# MotorControlV4_5.net
KiCad netlist of a schematic drawn in Altium Designer
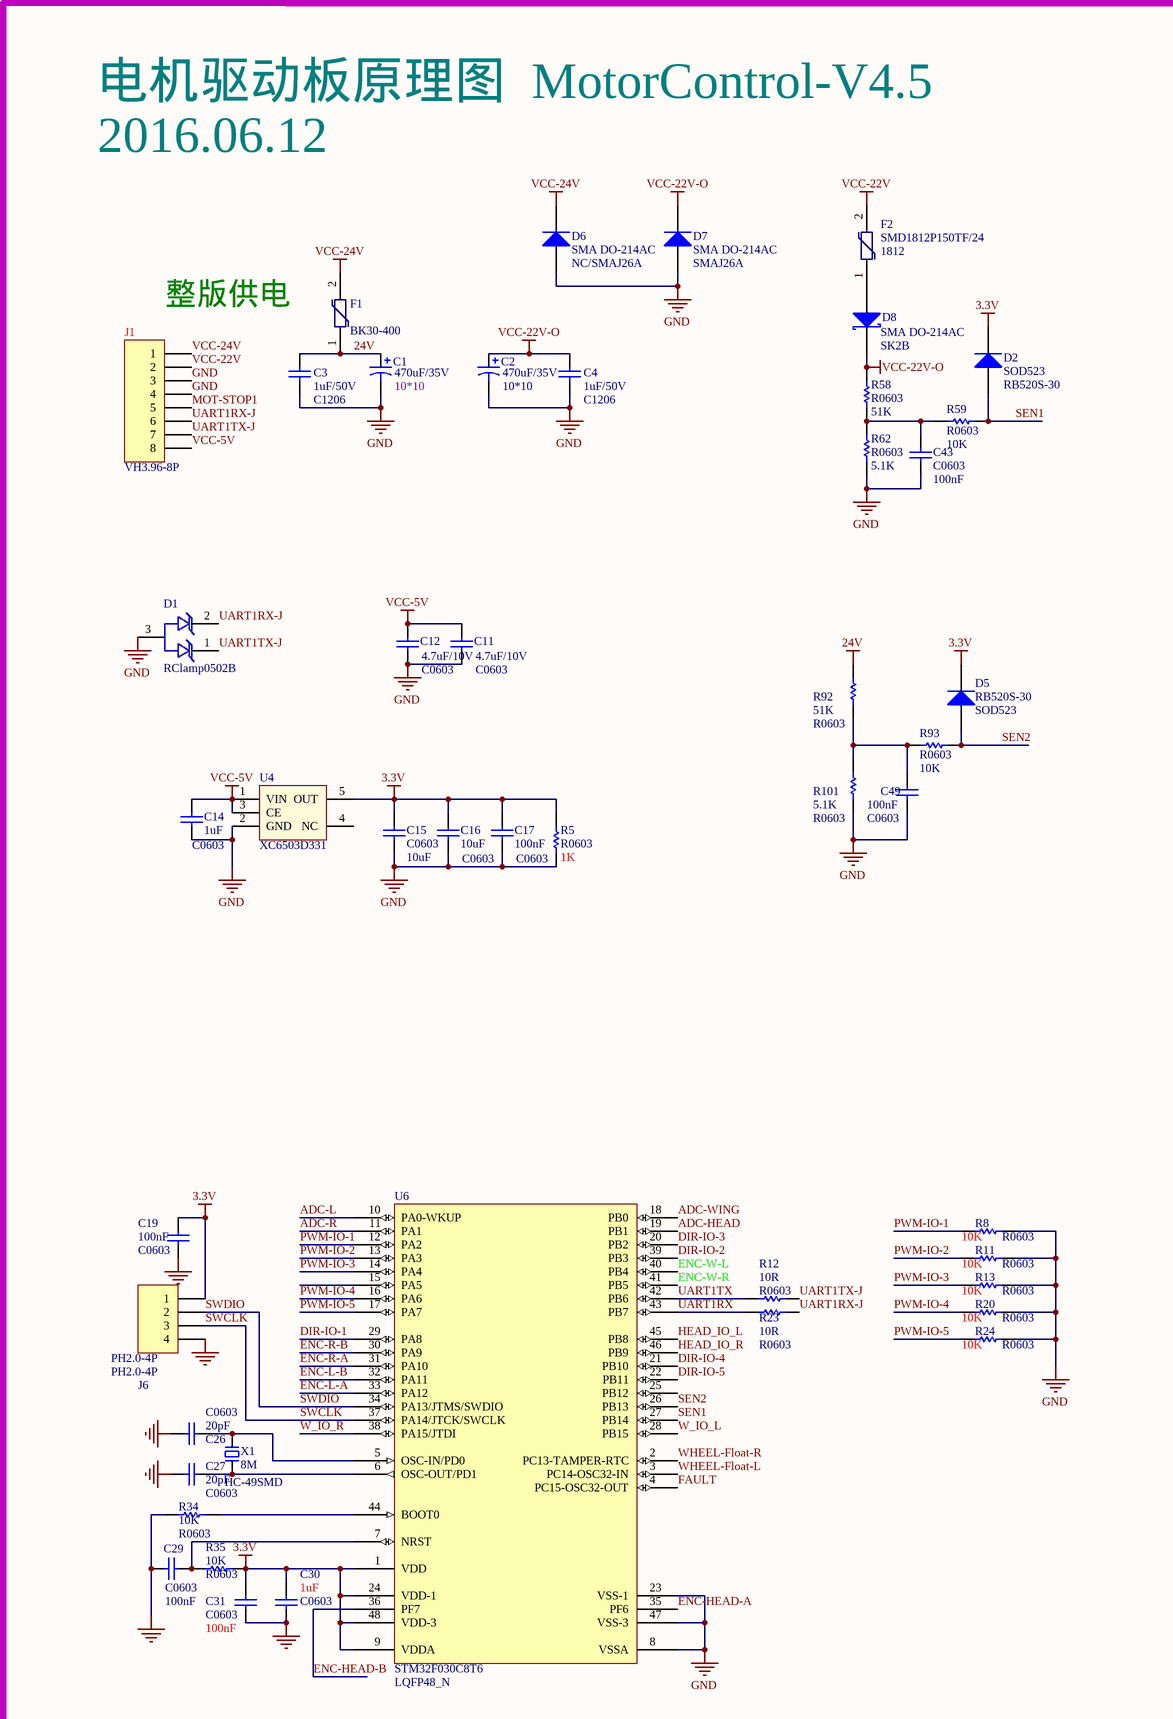
[diagram p0: MotorControlV4.5.SchDoc, top left]
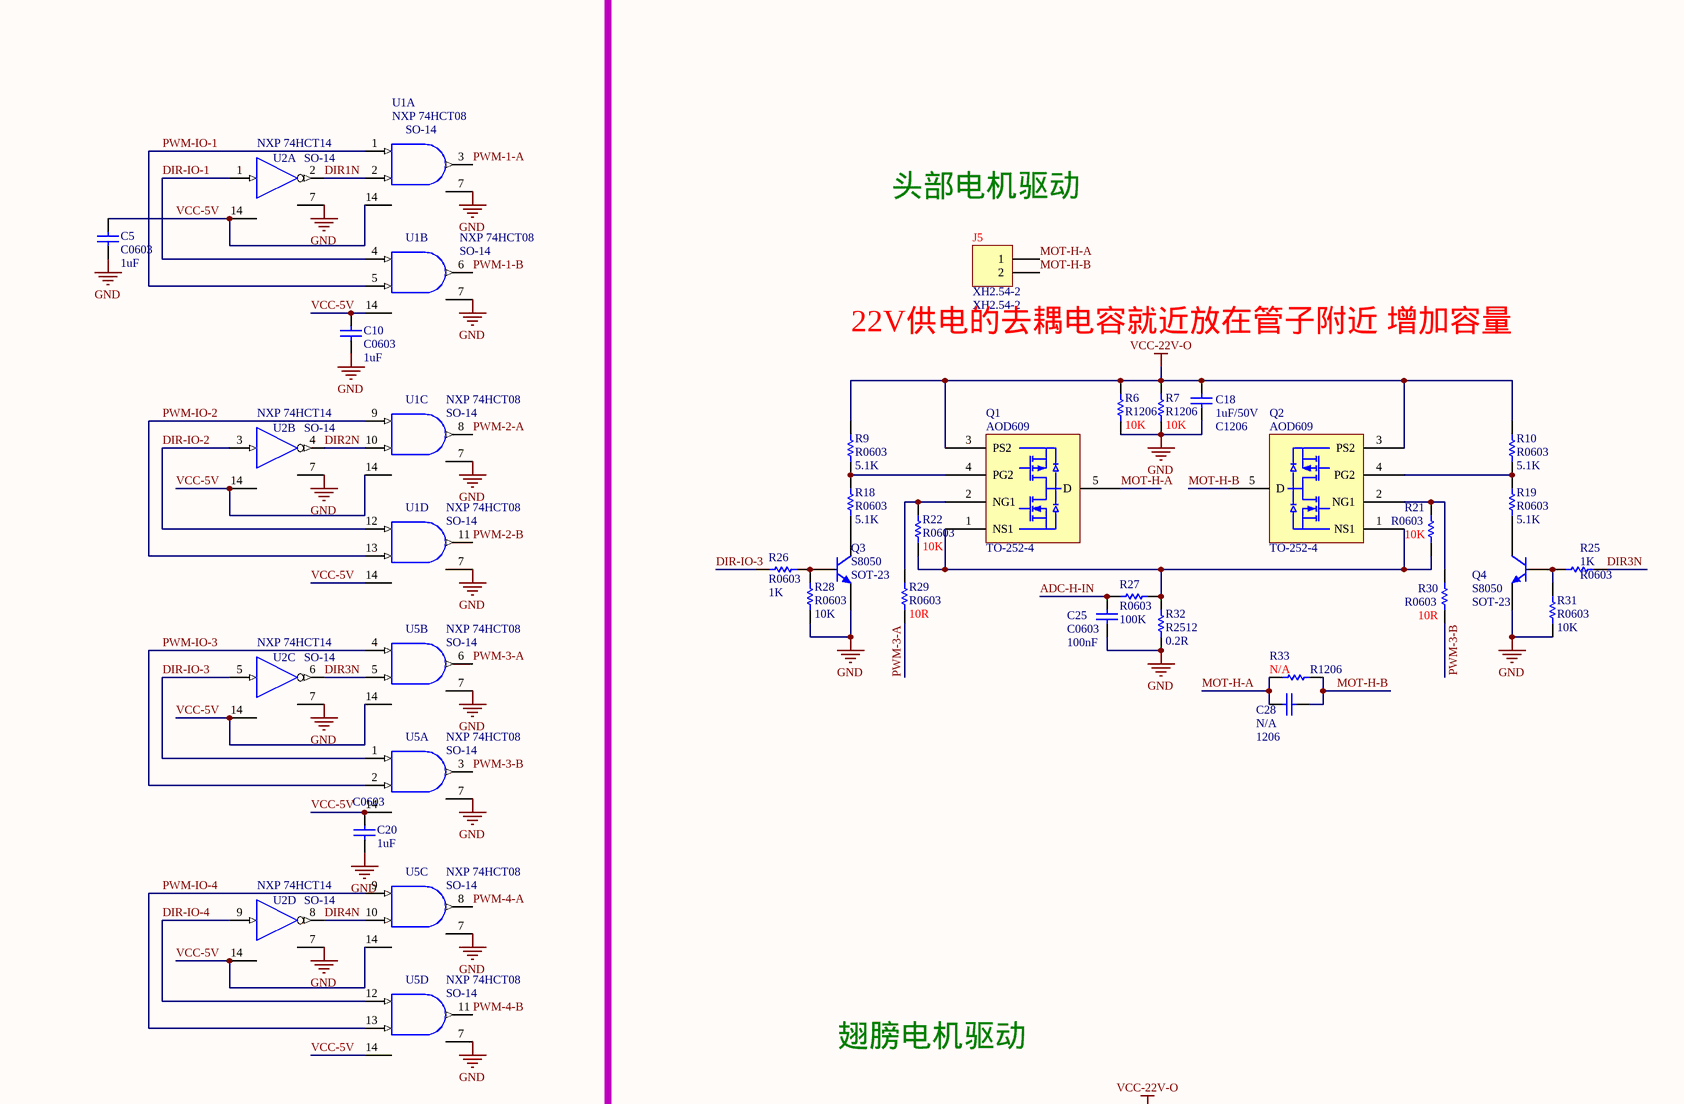
[diagram p1: MotorControlV4.5.SchDoc, top middle]
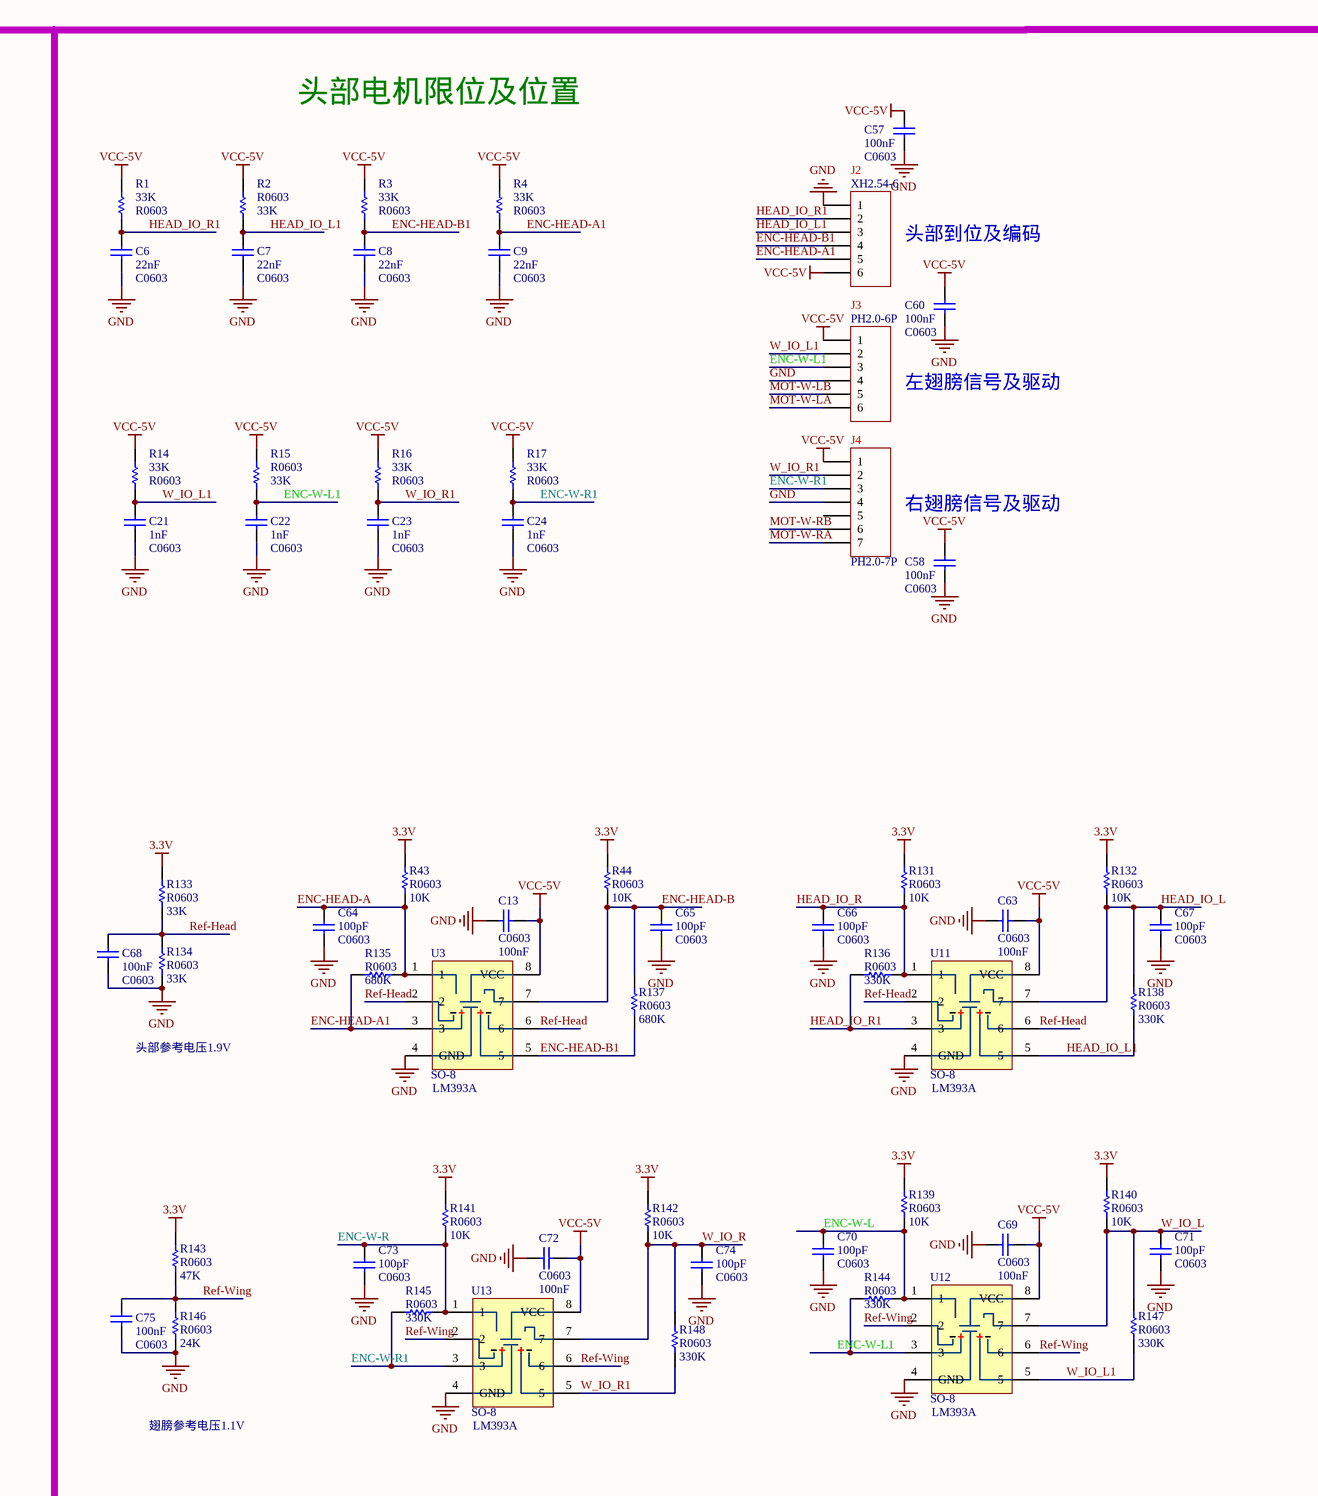
[diagram p2: MotorControlV4.5.SchDoc, top right]
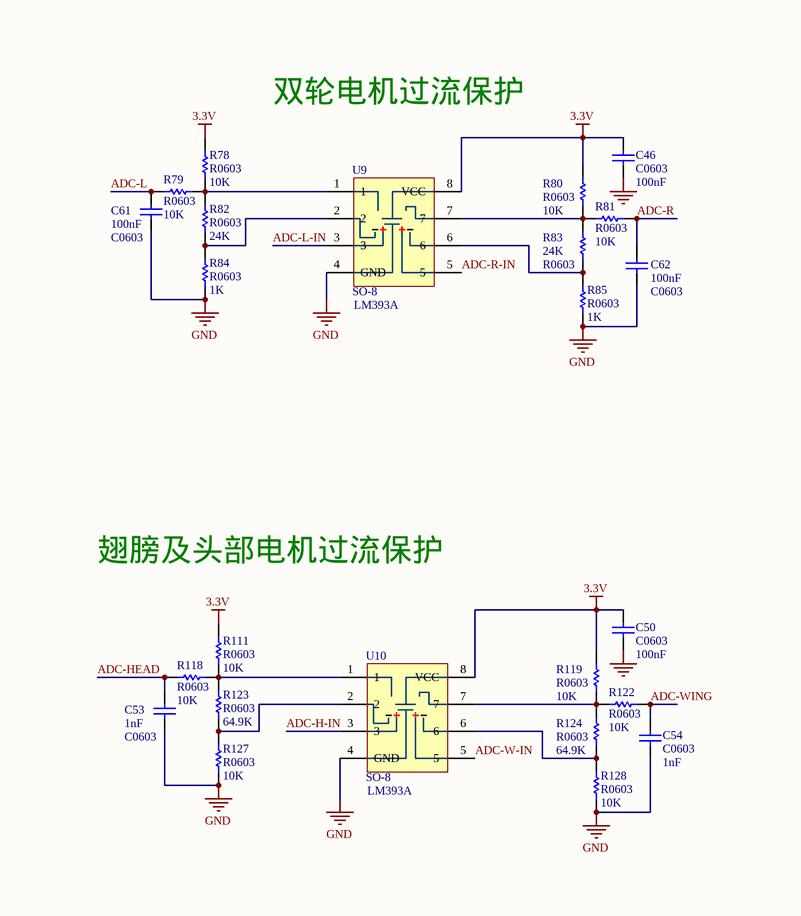
[diagram p3: MotorControlV4.5.SchDoc, bottom left]
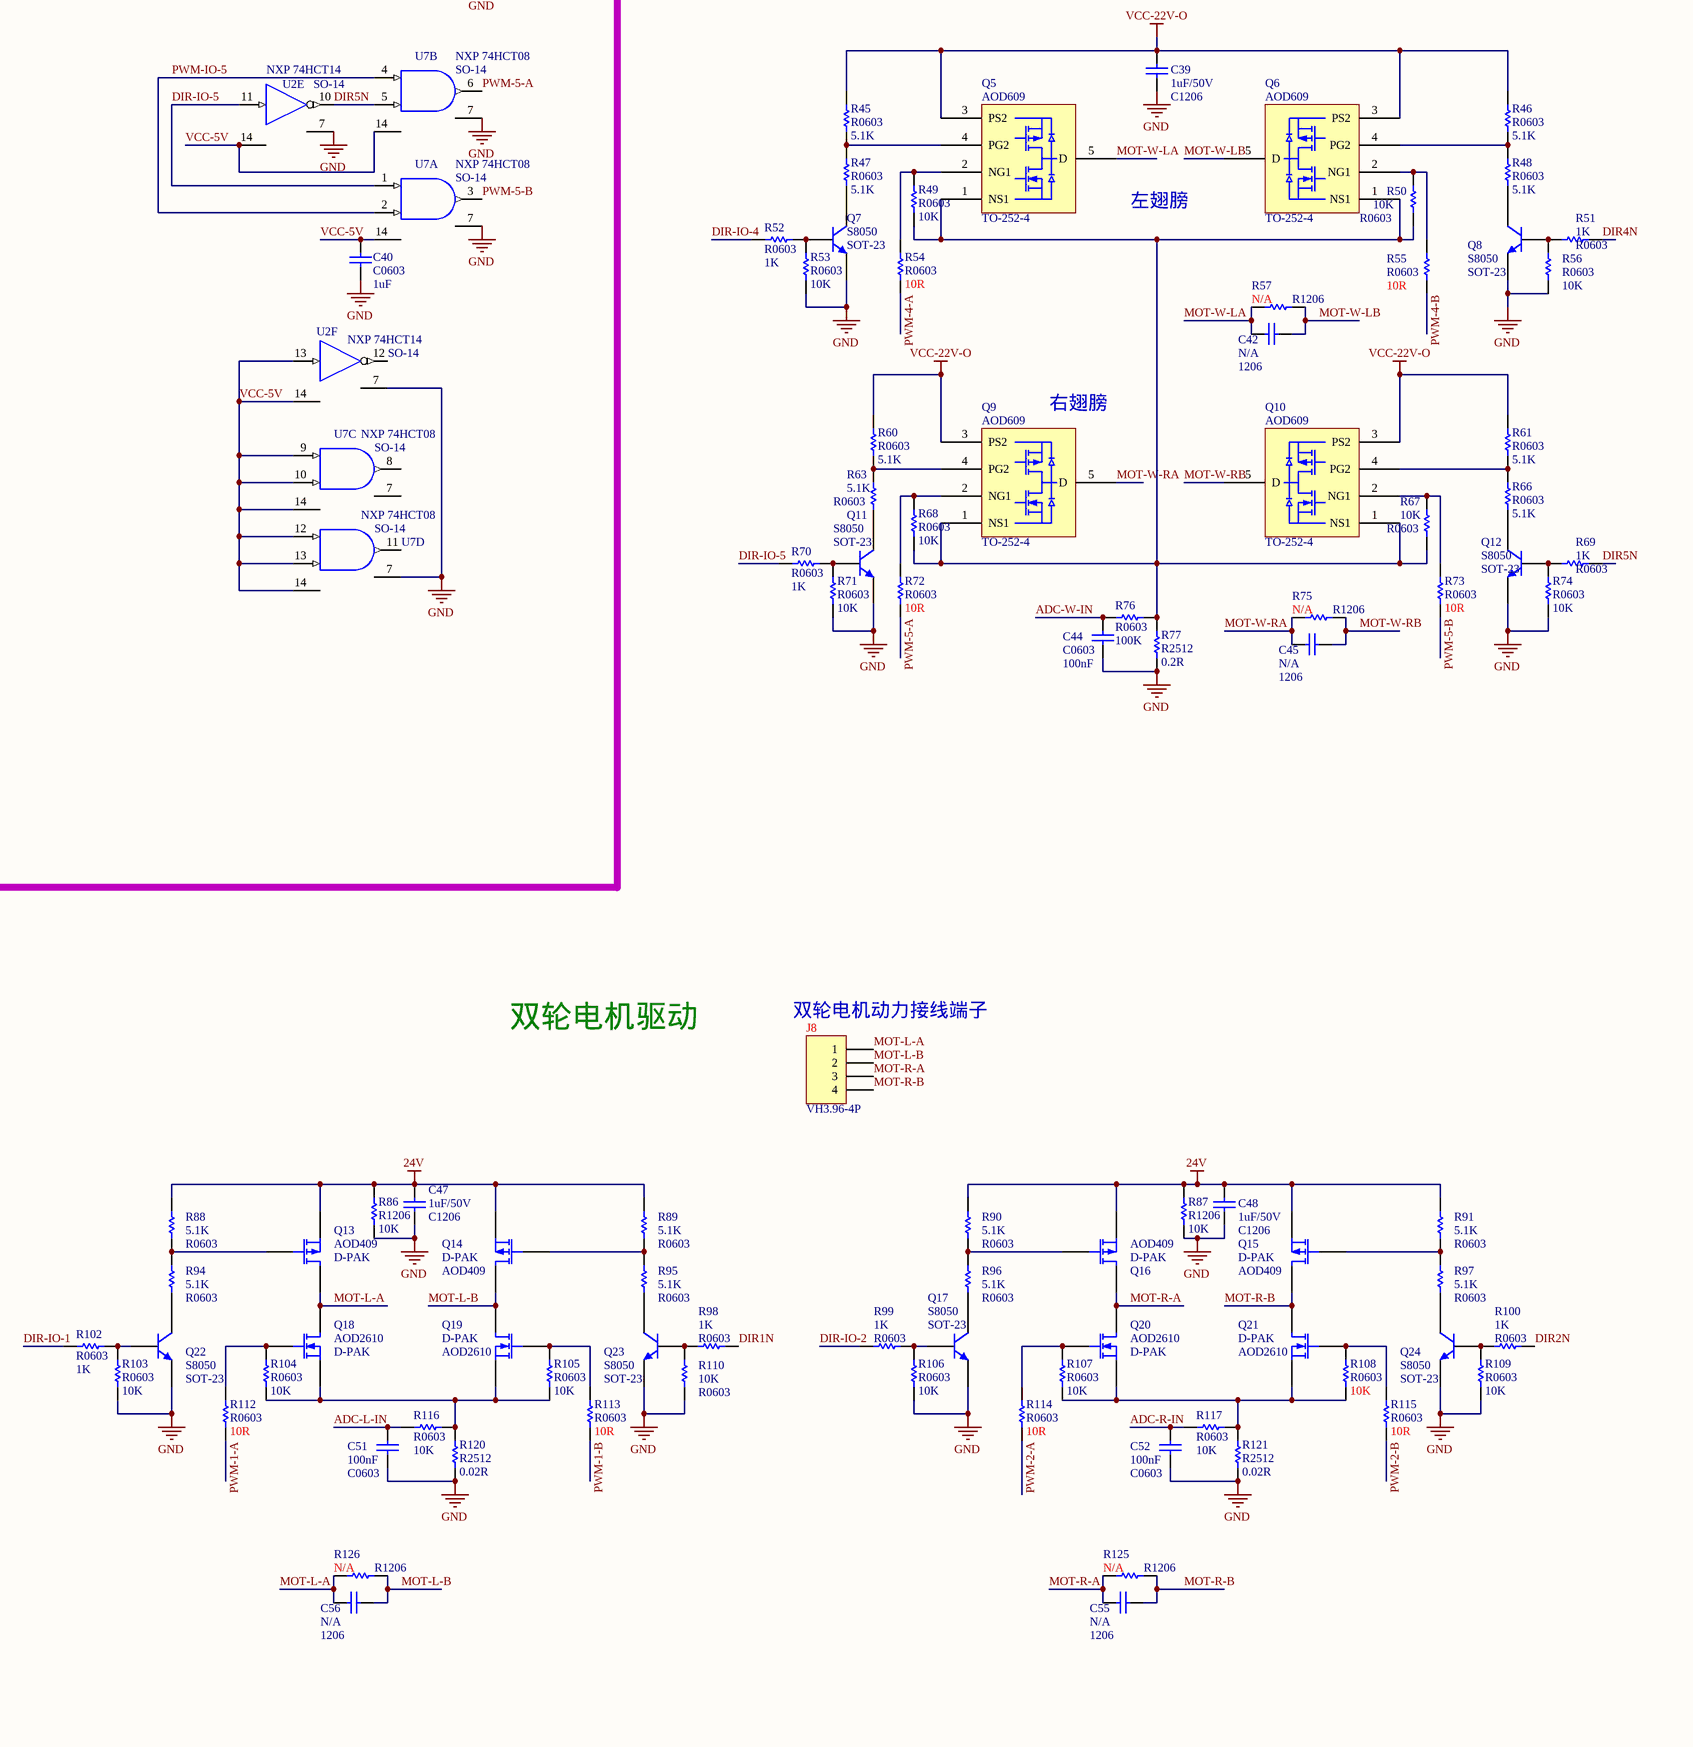
[diagram p4: MotorControlV4.5.SchDoc, bottom middle]
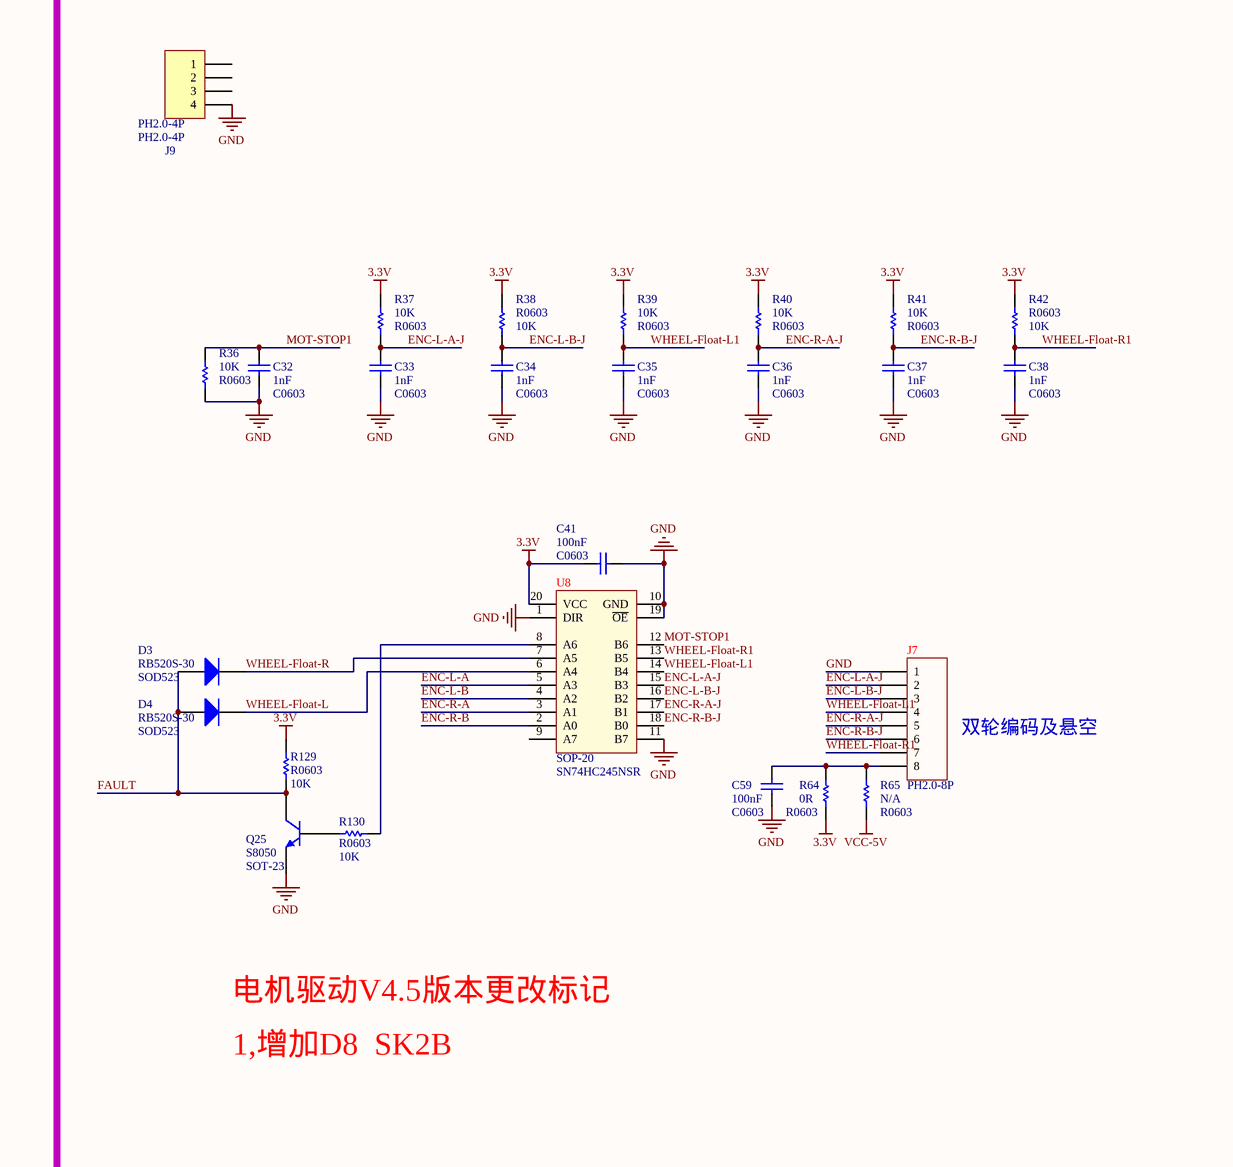
[diagram p5: MotorControlV4.5.SchDoc, bottom right]

(export (version "E")
  (design (tool "Eeschema 10.0.6"))
  (components
    (comp (ref "C1")
      (value "470uF/35V")
      (footprint "CAP_SO_10*10")
      (description "Polarized Capacitor (Surface Mount)")
      (fields (field (name "ALTIUM_VALUE") "10*10") (field (name "PUBLISHER") "Altium Limited"))
      (libsource (lib "Miscellaneous Devices") (part "Cap Pol3"))
    )
    (comp (ref "C2")
      (value "470uF/35V")
      (footprint "CAP_SO_10*10")
      (description "Polarized Capacitor (Surface Mount)")
      (fields (field (name "ALTIUM_VALUE") "10*10") (field (name "PUBLISHER") "Altium Limited"))
      (libsource (lib "Miscellaneous Devices") (part "Cap Pol3"))
    )
    (comp (ref "C3")
      (value "C1206")
      (footprint "1206")
      (description "Capacitor")
      (fields (field (name "ALTIUM_VALUE") "1uF/50V") (field (name "PUBLISHER") "Altium Limited"))
      (libsource (lib "Miscellaneous Devices") (part "Cap"))
    )
    (comp (ref "C4")
      (value "C1206")
      (footprint "1206")
      (description "Capacitor")
      (fields (field (name "ALTIUM_VALUE") "1uF/50V") (field (name "PUBLISHER") "Altium Limited"))
      (libsource (lib "Miscellaneous Devices") (part "Cap"))
    )
    (comp (ref "C5")
      (value "C0603")
      (footprint "C0603_M1608")
      (description "Capacitor")
      (fields (field (name "ALTIUM_VALUE") "1uF") (field (name "PUBLISHER") "Altium Limited"))
      (libsource (lib "Miscellaneous Devices") (part "Cap"))
    )
    (comp (ref "C6")
      (value "C0603")
      (footprint "C0603_M1608")
      (description "Capacitor")
      (fields (field (name "ALTIUM_VALUE") "22nF") (field (name "PUBLISHER") "Altium Limited"))
      (libsource (lib "Miscellaneous Devices") (part "Cap"))
    )
    (comp (ref "C7")
      (value "C0603")
      (footprint "C0603_M1608")
      (description "Capacitor")
      (fields (field (name "ALTIUM_VALUE") "22nF") (field (name "PUBLISHER") "Altium Limited"))
      (libsource (lib "Miscellaneous Devices") (part "Cap"))
    )
    (comp (ref "C8")
      (value "C0603")
      (footprint "C0603_M1608")
      (description "Capacitor")
      (fields (field (name "ALTIUM_VALUE") "22nF") (field (name "PUBLISHER") "Altium Limited"))
      (libsource (lib "Miscellaneous Devices") (part "Cap"))
    )
    (comp (ref "C9")
      (value "C0603")
      (footprint "C0603_M1608")
      (description "Capacitor")
      (fields (field (name "ALTIUM_VALUE") "22nF") (field (name "PUBLISHER") "Altium Limited"))
      (libsource (lib "Miscellaneous Devices") (part "Cap"))
    )
    (comp (ref "C10")
      (value "C0603")
      (footprint "C0603_M1608")
      (description "Capacitor")
      (fields (field (name "ALTIUM_VALUE") "1uF") (field (name "PUBLISHER") "Altium Limited"))
      (libsource (lib "Miscellaneous Devices") (part "Cap"))
    )
    (comp (ref "C11")
      (value "C0603")
      (footprint "C0603_M1608")
      (description "Capacitor")
      (fields (field (name "ALTIUM_VALUE") "4.7uF/10V") (field (name "PUBLISHER") "Altium Limited"))
      (libsource (lib "Miscellaneous Devices") (part "Cap"))
    )
    (comp (ref "C12")
      (value "C0603")
      (footprint "C0603_M1608")
      (description "Capacitor")
      (fields (field (name "ALTIUM_VALUE") "4.7uF/10V") (field (name "PUBLISHER") "Altium Limited"))
      (libsource (lib "Miscellaneous Devices") (part "Cap"))
    )
    (comp (ref "C13")
      (value "C0603")
      (footprint "C0603_M1608")
      (description "Capacitor")
      (fields (field (name "ALTIUM_VALUE") "100nF") (field (name "PUBLISHER") "Altium Limited"))
      (libsource (lib "Miscellaneous Devices") (part "Cap"))
    )
    (comp (ref "C14")
      (value "C0603")
      (footprint "C0603_M1608")
      (description "Capacitor")
      (fields (field (name "ALTIUM_VALUE") "1uF") (field (name "PUBLISHER") "Altium Limited"))
      (libsource (lib "Miscellaneous Devices") (part "Cap"))
    )
    (comp (ref "C15")
      (value "C0603")
      (footprint "C0603_M1608")
      (description "Capacitor")
      (fields (field (name "ALTIUM_VALUE") "10uF") (field (name "PUBLISHER") "Altium Limited"))
      (libsource (lib "Miscellaneous Devices") (part "Cap"))
    )
    (comp (ref "C16")
      (value "C0603")
      (footprint "C0603_M1608")
      (description "Capacitor")
      (fields (field (name "ALTIUM_VALUE") "10uF") (field (name "PUBLISHER") "Altium Limited"))
      (libsource (lib "Miscellaneous Devices") (part "Cap"))
    )
    (comp (ref "C17")
      (value "C0603")
      (footprint "C0603_M1608")
      (description "Capacitor")
      (fields (field (name "ALTIUM_VALUE") "100nF") (field (name "PUBLISHER") "Altium Limited"))
      (libsource (lib "Miscellaneous Devices") (part "Cap"))
    )
    (comp (ref "C18")
      (value "C1206")
      (footprint "1206")
      (description "Capacitor")
      (fields (field (name "ALTIUM_VALUE") "1uF/50V") (field (name "PUBLISHER") "Altium Limited"))
      (libsource (lib "Miscellaneous Devices") (part "Cap"))
    )
    (comp (ref "C19")
      (value "C0603")
      (footprint "C0603_M1608")
      (description "Capacitor")
      (fields (field (name "ALTIUM_VALUE") "100nF") (field (name "PUBLISHER") "Altium Limited"))
      (libsource (lib "Miscellaneous Devices") (part "Cap"))
    )
    (comp (ref "C20")
      (value "C0603")
      (footprint "C0603_M1608")
      (description "Capacitor")
      (fields (field (name "ALTIUM_VALUE") "1uF") (field (name "PUBLISHER") "Altium Limited"))
      (libsource (lib "Miscellaneous Devices") (part "Cap"))
    )
    (comp (ref "C21")
      (value "C0603")
      (footprint "C0603_M1608")
      (description "Capacitor")
      (fields (field (name "ALTIUM_VALUE") "1nF") (field (name "PUBLISHER") "Altium Limited"))
      (libsource (lib "Miscellaneous Devices") (part "Cap"))
    )
    (comp (ref "C22")
      (value "C0603")
      (footprint "C0603_M1608")
      (description "Capacitor")
      (fields (field (name "ALTIUM_VALUE") "1nF") (field (name "PUBLISHER") "Altium Limited"))
      (libsource (lib "Miscellaneous Devices") (part "Cap"))
    )
    (comp (ref "C23")
      (value "C0603")
      (footprint "C0603_M1608")
      (description "Capacitor")
      (fields (field (name "ALTIUM_VALUE") "1nF") (field (name "PUBLISHER") "Altium Limited"))
      (libsource (lib "Miscellaneous Devices") (part "Cap"))
    )
    (comp (ref "C24")
      (value "C0603")
      (footprint "C0603_M1608")
      (description "Capacitor")
      (fields (field (name "ALTIUM_VALUE") "1nF") (field (name "PUBLISHER") "Altium Limited"))
      (libsource (lib "Miscellaneous Devices") (part "Cap"))
    )
    (comp (ref "C25")
      (value "C0603")
      (footprint "C0603_M1608")
      (description "Capacitor")
      (fields (field (name "ALTIUM_VALUE") "100nF") (field (name "PUBLISHER") "Altium Limited"))
      (libsource (lib "Miscellaneous Devices") (part "Cap"))
    )
    (comp (ref "C26")
      (value "C0603")
      (footprint "C0603_M1608")
      (description "Capacitor")
      (fields (field (name "ALTIUM_VALUE") "20pF") (field (name "PUBLISHER") "Altium Limited"))
      (libsource (lib "Miscellaneous Devices") (part "Cap"))
    )
    (comp (ref "C27")
      (value "C0603")
      (footprint "C0603_M1608")
      (description "Capacitor")
      (fields (field (name "ALTIUM_VALUE") "20pF") (field (name "PUBLISHER") "Altium Limited"))
      (libsource (lib "Miscellaneous Devices") (part "Cap"))
    )
    (comp (ref "C28")
      (value "1206")
      (footprint "1206")
      (description "Capacitor")
      (fields (field (name "ALTIUM_VALUE") "N/A") (field (name "PUBLISHER") "Altium Limited"))
      (libsource (lib "Miscellaneous Devices") (part "Cap"))
    )
    (comp (ref "C29")
      (value "C0603")
      (footprint "C0603_M1608")
      (description "Capacitor")
      (fields (field (name "ALTIUM_VALUE") "100nF") (field (name "PUBLISHER") "Altium Limited"))
      (libsource (lib "Miscellaneous Devices") (part "Cap"))
    )
    (comp (ref "C30")
      (value "C0603")
      (footprint "C0603_M1608")
      (description "Capacitor")
      (fields (field (name "ALTIUM_VALUE") "1uF") (field (name "PUBLISHER") "Altium Limited"))
      (libsource (lib "Miscellaneous Devices") (part "Cap"))
    )
    (comp (ref "C31")
      (value "C0603")
      (footprint "C0603_M1608")
      (description "Capacitor")
      (fields (field (name "ALTIUM_VALUE") "100nF") (field (name "PUBLISHER") "Altium Limited"))
      (libsource (lib "Miscellaneous Devices") (part "Cap"))
    )
    (comp (ref "C32")
      (value "C0603")
      (footprint "C0603_M1608")
      (description "Capacitor")
      (fields (field (name "ALTIUM_VALUE") "1nF") (field (name "PUBLISHER") "Altium Limited"))
      (libsource (lib "Miscellaneous Devices") (part "Cap"))
    )
    (comp (ref "C33")
      (value "C0603")
      (footprint "C0603_M1608")
      (description "Capacitor")
      (fields (field (name "ALTIUM_VALUE") "1nF") (field (name "PUBLISHER") "Altium Limited"))
      (libsource (lib "Miscellaneous Devices") (part "Cap"))
    )
    (comp (ref "C34")
      (value "C0603")
      (footprint "C0603_M1608")
      (description "Capacitor")
      (fields (field (name "ALTIUM_VALUE") "1nF") (field (name "PUBLISHER") "Altium Limited"))
      (libsource (lib "Miscellaneous Devices") (part "Cap"))
    )
    (comp (ref "C35")
      (value "C0603")
      (footprint "C0603_M1608")
      (description "Capacitor")
      (fields (field (name "ALTIUM_VALUE") "1nF") (field (name "PUBLISHER") "Altium Limited"))
      (libsource (lib "Miscellaneous Devices") (part "Cap"))
    )
    (comp (ref "C36")
      (value "C0603")
      (footprint "C0603_M1608")
      (description "Capacitor")
      (fields (field (name "ALTIUM_VALUE") "1nF") (field (name "PUBLISHER") "Altium Limited"))
      (libsource (lib "Miscellaneous Devices") (part "Cap"))
    )
    (comp (ref "C37")
      (value "C0603")
      (footprint "C0603_M1608")
      (description "Capacitor")
      (fields (field (name "ALTIUM_VALUE") "1nF") (field (name "PUBLISHER") "Altium Limited"))
      (libsource (lib "Miscellaneous Devices") (part "Cap"))
    )
    (comp (ref "C38")
      (value "C0603")
      (footprint "C0603_M1608")
      (description "Capacitor")
      (fields (field (name "ALTIUM_VALUE") "1nF") (field (name "PUBLISHER") "Altium Limited"))
      (libsource (lib "Miscellaneous Devices") (part "Cap"))
    )
    (comp (ref "C39")
      (value "C1206")
      (footprint "1206")
      (description "Capacitor")
      (fields (field (name "ALTIUM_VALUE") "1uF/50V") (field (name "PUBLISHER") "Altium Limited"))
      (libsource (lib "Miscellaneous Devices") (part "Cap"))
    )
    (comp (ref "C40")
      (value "C0603")
      (footprint "C0603_M1608")
      (description "Capacitor")
      (fields (field (name "ALTIUM_VALUE") "1uF") (field (name "PUBLISHER") "Altium Limited"))
      (libsource (lib "Miscellaneous Devices") (part "Cap"))
    )
    (comp (ref "C41")
      (value "C0603")
      (footprint "C0603_M1608")
      (description "Capacitor")
      (fields (field (name "ALTIUM_VALUE") "100nF") (field (name "PUBLISHER") "Altium Limited"))
      (libsource (lib "Miscellaneous Devices") (part "Cap"))
    )
    (comp (ref "C42")
      (value "1206")
      (footprint "1206")
      (description "Capacitor")
      (fields (field (name "ALTIUM_VALUE") "N/A") (field (name "PUBLISHER") "Altium Limited"))
      (libsource (lib "Miscellaneous Devices") (part "Cap"))
    )
    (comp (ref "C43")
      (value "C0603")
      (footprint "C0603_M1608")
      (description "Capacitor")
      (fields (field (name "ALTIUM_VALUE") "100nF") (field (name "PUBLISHER") "Altium Limited"))
      (libsource (lib "Miscellaneous Devices") (part "Cap"))
    )
    (comp (ref "C44")
      (value "C0603")
      (footprint "C0603_M1608")
      (description "Capacitor")
      (fields (field (name "ALTIUM_VALUE") "100nF") (field (name "PUBLISHER") "Altium Limited"))
      (libsource (lib "Miscellaneous Devices") (part "Cap"))
    )
    (comp (ref "C45")
      (value "1206")
      (footprint "1206")
      (description "Capacitor")
      (fields (field (name "ALTIUM_VALUE") "N/A") (field (name "PUBLISHER") "Altium Limited"))
      (libsource (lib "Miscellaneous Devices") (part "Cap"))
    )
    (comp (ref "C46")
      (value "C0603")
      (footprint "C0603_M1608")
      (description "Capacitor")
      (fields (field (name "ALTIUM_VALUE") "100nF") (field (name "PUBLISHER") "Altium Limited"))
      (libsource (lib "Miscellaneous Devices") (part "Cap"))
    )
    (comp (ref "C47")
      (value "C1206")
      (footprint "1206")
      (description "Capacitor")
      (fields (field (name "ALTIUM_VALUE") "1uF/50V") (field (name "PUBLISHER") "Altium Limited"))
      (libsource (lib "Miscellaneous Devices") (part "Cap"))
    )
    (comp (ref "C48")
      (value "C1206")
      (footprint "1206")
      (description "Capacitor")
      (fields (field (name "ALTIUM_VALUE") "1uF/50V") (field (name "PUBLISHER") "Altium Limited"))
      (libsource (lib "Miscellaneous Devices") (part "Cap"))
    )
    (comp (ref "C49")
      (value "C0603")
      (footprint "C0603_M1608")
      (description "Capacitor")
      (fields (field (name "ALTIUM_VALUE") "100nF") (field (name "PUBLISHER") "Altium Limited"))
      (libsource (lib "Miscellaneous Devices") (part "Cap"))
    )
    (comp (ref "C50")
      (value "C0603")
      (footprint "C0603_M1608")
      (description "Capacitor")
      (fields (field (name "ALTIUM_VALUE") "100nF") (field (name "PUBLISHER") "Altium Limited"))
      (libsource (lib "Miscellaneous Devices") (part "Cap"))
    )
    (comp (ref "C51")
      (value "C0603")
      (footprint "C0603_M1608")
      (description "Capacitor")
      (fields (field (name "ALTIUM_VALUE") "100nF") (field (name "PUBLISHER") "Altium Limited"))
      (libsource (lib "Miscellaneous Devices") (part "Cap"))
    )
    (comp (ref "C52")
      (value "C0603")
      (footprint "C0603_M1608")
      (description "Capacitor")
      (fields (field (name "ALTIUM_VALUE") "100nF") (field (name "PUBLISHER") "Altium Limited"))
      (libsource (lib "Miscellaneous Devices") (part "Cap"))
    )
    (comp (ref "C53")
      (value "C0603")
      (footprint "C0603_M1608")
      (description "Capacitor")
      (fields (field (name "ALTIUM_VALUE") "1nF") (field (name "PUBLISHER") "Altium Limited"))
      (libsource (lib "Miscellaneous Devices") (part "Cap"))
    )
    (comp (ref "C54")
      (value "C0603")
      (footprint "C0603_M1608")
      (description "Capacitor")
      (fields (field (name "ALTIUM_VALUE") "1nF") (field (name "PUBLISHER") "Altium Limited"))
      (libsource (lib "Miscellaneous Devices") (part "Cap"))
    )
    (comp (ref "C55")
      (value "1206")
      (footprint "1206")
      (description "Capacitor")
      (fields (field (name "ALTIUM_VALUE") "N/A") (field (name "PUBLISHER") "Altium Limited"))
      (libsource (lib "Miscellaneous Devices") (part "Cap"))
    )
    (comp (ref "C56")
      (value "1206")
      (footprint "1206")
      (description "Capacitor")
      (fields (field (name "ALTIUM_VALUE") "N/A") (field (name "PUBLISHER") "Altium Limited"))
      (libsource (lib "Miscellaneous Devices") (part "Cap"))
    )
    (comp (ref "C57")
      (value "C0603")
      (footprint "C0603_M1608")
      (description "Capacitor")
      (fields (field (name "ALTIUM_VALUE") "100nF") (field (name "PUBLISHER") "Altium Limited"))
      (libsource (lib "Miscellaneous Devices") (part "Cap"))
    )
    (comp (ref "C58")
      (value "C0603")
      (footprint "C0603_M1608")
      (description "Capacitor")
      (fields (field (name "ALTIUM_VALUE") "100nF") (field (name "PUBLISHER") "Altium Limited"))
      (libsource (lib "Miscellaneous Devices") (part "Cap"))
    )
    (comp (ref "C59")
      (value "C0603")
      (footprint "C0603_M1608")
      (description "Capacitor")
      (fields (field (name "ALTIUM_VALUE") "100nF") (field (name "PUBLISHER") "Altium Limited"))
      (libsource (lib "Miscellaneous Devices") (part "Cap"))
    )
    (comp (ref "C60")
      (value "C0603")
      (footprint "C0603_M1608")
      (description "Capacitor")
      (fields (field (name "ALTIUM_VALUE") "100nF") (field (name "PUBLISHER") "Altium Limited"))
      (libsource (lib "Miscellaneous Devices") (part "Cap"))
    )
    (comp (ref "C61")
      (value "C0603")
      (footprint "C0603_M1608")
      (description "Capacitor")
      (fields (field (name "ALTIUM_VALUE") "100nF") (field (name "PUBLISHER") "Altium Limited"))
      (libsource (lib "Miscellaneous Devices") (part "Cap"))
    )
    (comp (ref "C62")
      (value "C0603")
      (footprint "C0603_M1608")
      (description "Capacitor")
      (fields (field (name "ALTIUM_VALUE") "100nF") (field (name "PUBLISHER") "Altium Limited"))
      (libsource (lib "Miscellaneous Devices") (part "Cap"))
    )
    (comp (ref "C63")
      (value "C0603")
      (footprint "C0603_M1608")
      (description "Capacitor")
      (fields (field (name "ALTIUM_VALUE") "100nF") (field (name "PUBLISHER") "Altium Limited"))
      (libsource (lib "Miscellaneous Devices") (part "Cap"))
    )
    (comp (ref "C64")
      (value "C0603")
      (footprint "C0603_M1608")
      (description "Capacitor")
      (fields (field (name "ALTIUM_VALUE") "100pF") (field (name "PUBLISHER") "Altium Limited"))
      (libsource (lib "Miscellaneous Devices") (part "Cap"))
    )
    (comp (ref "C65")
      (value "C0603")
      (footprint "C0603_M1608")
      (description "Capacitor")
      (fields (field (name "ALTIUM_VALUE") "100pF") (field (name "PUBLISHER") "Altium Limited"))
      (libsource (lib "Miscellaneous Devices") (part "Cap"))
    )
    (comp (ref "C66")
      (value "C0603")
      (footprint "C0603_M1608")
      (description "Capacitor")
      (fields (field (name "ALTIUM_VALUE") "100pF") (field (name "PUBLISHER") "Altium Limited"))
      (libsource (lib "Miscellaneous Devices") (part "Cap"))
    )
    (comp (ref "C67")
      (value "C0603")
      (footprint "C0603_M1608")
      (description "Capacitor")
      (fields (field (name "ALTIUM_VALUE") "100pF") (field (name "PUBLISHER") "Altium Limited"))
      (libsource (lib "Miscellaneous Devices") (part "Cap"))
    )
    (comp (ref "C68")
      (value "C0603")
      (footprint "C0603_M1608")
      (description "Capacitor")
      (fields (field (name "ALTIUM_VALUE") "100nF") (field (name "PUBLISHER") "Altium Limited"))
      (libsource (lib "Miscellaneous Devices") (part "Cap"))
    )
    (comp (ref "C69")
      (value "C0603")
      (footprint "C0603_M1608")
      (description "Capacitor")
      (fields (field (name "ALTIUM_VALUE") "100nF") (field (name "PUBLISHER") "Altium Limited"))
      (libsource (lib "Miscellaneous Devices") (part "Cap"))
    )
    (comp (ref "C70")
      (value "C0603")
      (footprint "C0603_M1608")
      (description "Capacitor")
      (fields (field (name "ALTIUM_VALUE") "100pF") (field (name "PUBLISHER") "Altium Limited"))
      (libsource (lib "Miscellaneous Devices") (part "Cap"))
    )
    (comp (ref "C71")
      (value "C0603")
      (footprint "C0603_M1608")
      (description "Capacitor")
      (fields (field (name "ALTIUM_VALUE") "100pF") (field (name "PUBLISHER") "Altium Limited"))
      (libsource (lib "Miscellaneous Devices") (part "Cap"))
    )
    (comp (ref "C72")
      (value "C0603")
      (footprint "C0603_M1608")
      (description "Capacitor")
      (fields (field (name "ALTIUM_VALUE") "100nF") (field (name "PUBLISHER") "Altium Limited"))
      (libsource (lib "Miscellaneous Devices") (part "Cap"))
    )
    (comp (ref "C73")
      (value "C0603")
      (footprint "C0603_M1608")
      (description "Capacitor")
      (fields (field (name "ALTIUM_VALUE") "100pF") (field (name "PUBLISHER") "Altium Limited"))
      (libsource (lib "Miscellaneous Devices") (part "Cap"))
    )
    (comp (ref "C74")
      (value "C0603")
      (footprint "C0603_M1608")
      (description "Capacitor")
      (fields (field (name "ALTIUM_VALUE") "100pF") (field (name "PUBLISHER") "Altium Limited"))
      (libsource (lib "Miscellaneous Devices") (part "Cap"))
    )
    (comp (ref "C75")
      (value "C0603")
      (footprint "C0603_M1608")
      (description "Capacitor")
      (fields (field (name "ALTIUM_VALUE") "100nF") (field (name "PUBLISHER") "Altium Limited"))
      (libsource (lib "Miscellaneous Devices") (part "Cap"))
    )
    (comp (ref "D1") (value "RClamp0502B") (footprint "SOT-523") (libsource (lib "SCH") (part "LCTVS")))
    (comp (ref "D2")
      (value "SOD523")
      (footprint "SOD523")
      (description "Default Diode")
      (fields (field (name "ALTIUM_VALUE") "RB520S-30") (field (name "PUBLISHER") "Altium Limited"))
      (libsource (lib "SCH") (part "Diode"))
    )
    (comp (ref "D3")
      (value "SOD523")
      (footprint "SOD523")
      (description "Default Diode")
      (fields (field (name "ALTIUM_VALUE") "RB520S-30") (field (name "PUBLISHER") "Altium Limited"))
      (libsource (lib "") (part "Diode_1"))
    )
    (comp (ref "D4")
      (value "SOD523")
      (footprint "SOD523")
      (description "Default Diode")
      (fields (field (name "ALTIUM_VALUE") "RB520S-30") (field (name "PUBLISHER") "Altium Limited"))
      (libsource (lib "") (part "Diode_1"))
    )
    (comp (ref "D5")
      (value "SOD523")
      (footprint "SOD523")
      (description "Default Diode")
      (fields (field (name "ALTIUM_VALUE") "RB520S-30") (field (name "PUBLISHER") "Altium Limited"))
      (libsource (lib "SCH") (part "Diode"))
    )
    (comp (ref "D6")
      (value "SMA DO-214AC")
      (footprint "SMA DO-214AC")
      (description "Default Diode")
      (fields (field (name "ALTIUM_VALUE") "NC/SMAJ26A") (field (name "PUBLISHER") "Altium Limited"))
      (libsource (lib "SCH") (part "Diode"))
    )
    (comp (ref "D7")
      (value "SMA DO-214AC")
      (footprint "SMA DO-214AC")
      (description "Default Diode")
      (fields (field (name "ALTIUM_VALUE") "SMAJ26A") (field (name "PUBLISHER") "Altium Limited"))
      (libsource (lib "SCH") (part "Diode"))
    )
    (comp (ref "D8")
      (value "SMA DO-214AC")
      (footprint "SMA DO-214AC")
      (description "Schottky Diode")
      (fields (field (name "ALTIUM_VALUE") "SK2B") (field (name "PUBLISHER") "Altium Limited"))
      (libsource (lib "Miscellaneous Devices") (part "D Schottky"))
    )
    (comp (ref "F1") (value "BK30-400") (footprint "FUSE-FRG-5MM") (libsource (lib "SCH") (part "PPTC")))
    (comp (ref "F2")
      (value "1812")
      (footprint "1812")
      (fields (field (name "ALTIUM_VALUE") "SMD1812P150TF/24"))
      (libsource (lib "SCH") (part "PPTC"))
    )
    (comp (ref "J1") (value "VH3.96-8P") (footprint "VH3.96-8P") (libsource (lib "SCH") (part "VH3.96-8P")))
    (comp (ref "J2")
      (value "XH2.54-6")
      (footprint "XH2.54-6")
      (description "Header, 6-Pin")
      (fields (field (name "PUBLISHER") "Altium Limited"))
      (libsource (lib "SCH") (part "PH2.0-6P"))
    )
    (comp (ref "J3")
      (value "PH2.0-6P")
      (footprint "PH2.0-6P")
      (description "Header, 6-Pin")
      (fields (field (name "PUBLISHER") "Altium Limited"))
      (libsource (lib "SCH") (part "PH2.0-6P"))
    )
    (comp (ref "J4")
      (value "PH2.0-7P")
      (footprint "PH2.0-7P")
      (description "Header, 7-Pin")
      (fields (field (name "PUBLISHER") "Altium Limited"))
      (libsource (lib "SCH") (part "PH2.0-7P"))
    )
    (comp (ref "J5")
      (value "XH2.54-2")
      (footprint "XH2.54-2")
      (description "Header, 2-Pin")
      (fields (field (name "ALTIUM_VALUE") "XH2.54-2") (field (name "PUBLISHER") "Altium Limited"))
      (libsource (lib "SCH") (part "XH2P"))
    )
    (comp (ref "J6")
      (value "PH2.0-4P")
      (footprint "PH2.0-4P")
      (description "Header, 4-Pin")
      (fields (field (name "ALTIUM_VALUE") "PH2.0-4P") (field (name "PUBLISHER") "Altium Limited"))
      (libsource (lib "Miscellaneous Connectors") (part "Header 4"))
    )
    (comp (ref "J7")
      (value "PH2.0-8P")
      (footprint "PH2.0-8P")
      (description "Header, 6-Pin")
      (fields (field (name "PUBLISHER") "Altium Limited"))
      (libsource (lib "SCH") (part "PH2.0-8P"))
    )
    (comp (ref "J8")
      (value "VH3.96-4P")
      (footprint "VH3.96-4P")
      (description "Header, 3-Pin")
      (fields (field (name "PUBLISHER") "Altium Limited"))
      (libsource (lib "SCH") (part "VH3.96-4P"))
    )
    (comp (ref "J9")
      (value "PH2.0-4P")
      (footprint "PH2.0-4P")
      (description "Header, 4-Pin")
      (fields (field (name "ALTIUM_VALUE") "PH2.0-4P") (field (name "PUBLISHER") "Altium Limited"))
      (libsource (lib "Miscellaneous Connectors") (part "Header 4"))
    )
    (comp (ref "Q1")
      (value "TO-252-4")
      (footprint "TO-252-4L")
      (fields (field (name "ALTIUM_VALUE") "AOD609"))
      (libsource (lib "") (part "MOS-DUAL-N/P_1"))
    )
    (comp (ref "Q2")
      (value "TO-252-4")
      (footprint "TO-252-4L")
      (fields (field (name "ALTIUM_VALUE") "AOD609"))
      (libsource (lib "CYSchlib") (part "MOS-DUAL-N/P"))
    )
    (comp (ref "Q3")
      (value "SOT-23")
      (footprint "SOT-23_L")
      (description "NPN Bipolar Transistor")
      (fields (field (name "ALTIUM_VALUE") "S8050") (field (name "PUBLISHER") "Altium Limited"))
      (libsource (lib "CYSchlib") (part "NPN"))
    )
    (comp (ref "Q4")
      (value "SOT-23")
      (footprint "SOT-23_L")
      (description "NPN Bipolar Transistor")
      (fields (field (name "ALTIUM_VALUE") "S8050") (field (name "PUBLISHER") "Altium Limited"))
      (libsource (lib "CYSchlib") (part "NPN"))
    )
    (comp (ref "Q5")
      (value "TO-252-4")
      (footprint "TO-252-4L")
      (fields (field (name "ALTIUM_VALUE") "AOD609"))
      (libsource (lib "") (part "MOS-DUAL-N/P_1"))
    )
    (comp (ref "Q6")
      (value "TO-252-4")
      (footprint "TO-252-4L")
      (fields (field (name "ALTIUM_VALUE") "AOD609"))
      (libsource (lib "CYSchlib") (part "MOS-DUAL-N/P"))
    )
    (comp (ref "Q7")
      (value "SOT-23")
      (footprint "SOT-23_L")
      (description "NPN Bipolar Transistor")
      (fields (field (name "ALTIUM_VALUE") "S8050") (field (name "PUBLISHER") "Altium Limited"))
      (libsource (lib "CYSchlib") (part "NPN"))
    )
    (comp (ref "Q8")
      (value "SOT-23")
      (footprint "SOT-23_L")
      (description "NPN Bipolar Transistor")
      (fields (field (name "ALTIUM_VALUE") "S8050") (field (name "PUBLISHER") "Altium Limited"))
      (libsource (lib "CYSchlib") (part "NPN"))
    )
    (comp (ref "Q9")
      (value "TO-252-4")
      (footprint "TO-252-4L")
      (fields (field (name "ALTIUM_VALUE") "AOD609"))
      (libsource (lib "") (part "MOS-DUAL-N/P_1"))
    )
    (comp (ref "Q10")
      (value "TO-252-4")
      (footprint "TO-252-4L")
      (fields (field (name "ALTIUM_VALUE") "AOD609"))
      (libsource (lib "CYSchlib") (part "MOS-DUAL-N/P"))
    )
    (comp (ref "Q11")
      (value "SOT-23")
      (footprint "SOT-23_L")
      (description "NPN Bipolar Transistor")
      (fields (field (name "ALTIUM_VALUE") "S8050") (field (name "PUBLISHER") "Altium Limited"))
      (libsource (lib "CYSchlib") (part "NPN"))
    )
    (comp (ref "Q12")
      (value "SOT-23")
      (footprint "SOT-23_L")
      (description "NPN Bipolar Transistor")
      (fields (field (name "ALTIUM_VALUE") "S8050") (field (name "PUBLISHER") "Altium Limited"))
      (libsource (lib "CYSchlib") (part "NPN"))
    )
    (comp (ref "Q13")
      (value "D-PAK")
      (footprint "TO-252-2L")
      (description "P-Channel MOSFET")
      (fields (field (name "ALTIUM_VALUE") "AOD409") (field (name "PUBLISHER") "Altium Limited"))
      (libsource (lib "CYSchlib") (part "MOS-P"))
    )
    (comp (ref "Q14")
      (value "D-PAK")
      (footprint "TO-252-2L")
      (description "P-Channel MOSFET")
      (fields (field (name "ALTIUM_VALUE") "AOD409") (field (name "PUBLISHER") "Altium Limited"))
      (libsource (lib "CYSchlib") (part "MOS-P"))
    )
    (comp (ref "Q15")
      (value "D-PAK")
      (footprint "TO-252-2L")
      (description "P-Channel MOSFET")
      (fields (field (name "ALTIUM_VALUE") "AOD409") (field (name "PUBLISHER") "Altium Limited"))
      (libsource (lib "CYSchlib") (part "MOS-P"))
    )
    (comp (ref "Q16")
      (value "D-PAK")
      (footprint "TO-252-2L")
      (description "P-Channel MOSFET")
      (fields (field (name "ALTIUM_VALUE") "AOD409") (field (name "PUBLISHER") "Altium Limited"))
      (libsource (lib "CYSchlib") (part "MOS-P"))
    )
    (comp (ref "Q17")
      (value "SOT-23")
      (footprint "SOT-23_L")
      (description "NPN Bipolar Transistor")
      (fields (field (name "ALTIUM_VALUE") "S8050") (field (name "PUBLISHER") "Altium Limited"))
      (libsource (lib "CYSchlib") (part "NPN"))
    )
    (comp (ref "Q18")
      (value "D-PAK")
      (footprint "TO-252-2L")
      (description "N-Channel MOSFET")
      (fields (field (name "ALTIUM_VALUE") "AOD2610") (field (name "PUBLISHER") "Altium Limited"))
      (libsource (lib "CYSchlib") (part "MOS-N"))
    )
    (comp (ref "Q19")
      (value "D-PAK")
      (footprint "TO-252-2L")
      (description "N-Channel MOSFET")
      (fields (field (name "ALTIUM_VALUE") "AOD2610") (field (name "PUBLISHER") "Altium Limited"))
      (libsource (lib "CYSchlib") (part "MOS-N"))
    )
    (comp (ref "Q20")
      (value "D-PAK")
      (footprint "TO-252-2L")
      (description "N-Channel MOSFET")
      (fields (field (name "ALTIUM_VALUE") "AOD2610") (field (name "PUBLISHER") "Altium Limited"))
      (libsource (lib "CYSchlib") (part "MOS-N"))
    )
    (comp (ref "Q21")
      (value "D-PAK")
      (footprint "TO-252-2L")
      (description "N-Channel MOSFET")
      (fields (field (name "ALTIUM_VALUE") "AOD2610") (field (name "PUBLISHER") "Altium Limited"))
      (libsource (lib "CYSchlib") (part "MOS-N"))
    )
    (comp (ref "Q22")
      (value "SOT-23")
      (footprint "SOT-23_L")
      (description "NPN Bipolar Transistor")
      (fields (field (name "ALTIUM_VALUE") "S8050") (field (name "PUBLISHER") "Altium Limited"))
      (libsource (lib "CYSchlib") (part "NPN"))
    )
    (comp (ref "Q23")
      (value "SOT-23")
      (footprint "SOT-23_L")
      (description "NPN Bipolar Transistor")
      (fields (field (name "ALTIUM_VALUE") "S8050") (field (name "PUBLISHER") "Altium Limited"))
      (libsource (lib "CYSchlib") (part "NPN"))
    )
    (comp (ref "Q24")
      (value "SOT-23")
      (footprint "SOT-23_L")
      (description "NPN Bipolar Transistor")
      (fields (field (name "ALTIUM_VALUE") "S8050") (field (name "PUBLISHER") "Altium Limited"))
      (libsource (lib "CYSchlib") (part "NPN"))
    )
    (comp (ref "Q25")
      (value "SOT-23")
      (footprint "SOT-23_L")
      (description "NPN Bipolar Transistor")
      (fields (field (name "ALTIUM_VALUE") "S8050") (field (name "PUBLISHER") "Altium Limited"))
      (libsource (lib "CYSchlib") (part "NPN"))
    )
    (comp (ref "R1")
      (value "R0603")
      (footprint "0603")
      (description "Resistor")
      (fields (field (name "ALTIUM_VALUE") "33K") (field (name "PUBLISHER") "Altium Limited"))
      (libsource (lib "Miscellaneous Devices") (part "Res1"))
    )
    (comp (ref "R2")
      (value "R0603")
      (footprint "0603")
      (description "Resistor")
      (fields (field (name "ALTIUM_VALUE") "33K") (field (name "PUBLISHER") "Altium Limited"))
      (libsource (lib "Miscellaneous Devices") (part "Res1"))
    )
    (comp (ref "R3")
      (value "R0603")
      (footprint "0603")
      (description "Resistor")
      (fields (field (name "ALTIUM_VALUE") "33K") (field (name "PUBLISHER") "Altium Limited"))
      (libsource (lib "Miscellaneous Devices") (part "Res1"))
    )
    (comp (ref "R4")
      (value "R0603")
      (footprint "0603")
      (description "Resistor")
      (fields (field (name "ALTIUM_VALUE") "33K") (field (name "PUBLISHER") "Altium Limited"))
      (libsource (lib "Miscellaneous Devices") (part "Res1"))
    )
    (comp (ref "R5")
      (value "R0603")
      (footprint "0603")
      (description "Resistor")
      (fields (field (name "ALTIUM_VALUE") "1K") (field (name "PUBLISHER") "Altium Limited"))
      (libsource (lib "Miscellaneous Devices") (part "Res1"))
    )
    (comp (ref "R6")
      (value "R1206")
      (footprint "1206")
      (description "Resistor")
      (fields (field (name "ALTIUM_VALUE") "10K") (field (name "PUBLISHER") "Altium Limited"))
      (libsource (lib "Miscellaneous Devices") (part "Res1"))
    )
    (comp (ref "R7")
      (value "R1206")
      (footprint "1206")
      (description "Resistor")
      (fields (field (name "ALTIUM_VALUE") "10K") (field (name "PUBLISHER") "Altium Limited"))
      (libsource (lib "Miscellaneous Devices") (part "Res1"))
    )
    (comp (ref "R8")
      (value "R0603")
      (footprint "0603")
      (description "Resistor")
      (fields (field (name "ALTIUM_VALUE") "10K") (field (name "PUBLISHER") "Altium Limited"))
      (libsource (lib "Miscellaneous Devices") (part "Res1"))
    )
    (comp (ref "R9")
      (value "R0603")
      (footprint "0603")
      (description "Resistor")
      (fields (field (name "ALTIUM_VALUE") "5.1K") (field (name "PUBLISHER") "Altium Limited"))
      (libsource (lib "Miscellaneous Devices") (part "Res1"))
    )
    (comp (ref "R10")
      (value "R0603")
      (footprint "0603")
      (description "Resistor")
      (fields (field (name "ALTIUM_VALUE") "5.1K") (field (name "PUBLISHER") "Altium Limited"))
      (libsource (lib "Miscellaneous Devices") (part "Res1"))
    )
    (comp (ref "R11")
      (value "R0603")
      (footprint "0603")
      (description "Resistor")
      (fields (field (name "ALTIUM_VALUE") "10K") (field (name "PUBLISHER") "Altium Limited"))
      (libsource (lib "Miscellaneous Devices") (part "Res1"))
    )
    (comp (ref "R12")
      (value "R0603")
      (footprint "0603")
      (description "Resistor")
      (fields (field (name "ALTIUM_VALUE") "10R") (field (name "PUBLISHER") "Altium Limited"))
      (libsource (lib "Miscellaneous Devices") (part "Res1"))
    )
    (comp (ref "R13")
      (value "R0603")
      (footprint "0603")
      (description "Resistor")
      (fields (field (name "ALTIUM_VALUE") "10K") (field (name "PUBLISHER") "Altium Limited"))
      (libsource (lib "Miscellaneous Devices") (part "Res1"))
    )
    (comp (ref "R14")
      (value "R0603")
      (footprint "0603")
      (description "Resistor")
      (fields (field (name "ALTIUM_VALUE") "33K") (field (name "PUBLISHER") "Altium Limited"))
      (libsource (lib "Miscellaneous Devices") (part "Res1"))
    )
    (comp (ref "R15")
      (value "R0603")
      (footprint "0603")
      (description "Resistor")
      (fields (field (name "ALTIUM_VALUE") "33K") (field (name "PUBLISHER") "Altium Limited"))
      (libsource (lib "Miscellaneous Devices") (part "Res1"))
    )
    (comp (ref "R16")
      (value "R0603")
      (footprint "0603")
      (description "Resistor")
      (fields (field (name "ALTIUM_VALUE") "33K") (field (name "PUBLISHER") "Altium Limited"))
      (libsource (lib "Miscellaneous Devices") (part "Res1"))
    )
    (comp (ref "R17")
      (value "R0603")
      (footprint "0603")
      (description "Resistor")
      (fields (field (name "ALTIUM_VALUE") "33K") (field (name "PUBLISHER") "Altium Limited"))
      (libsource (lib "Miscellaneous Devices") (part "Res1"))
    )
    (comp (ref "R18")
      (value "R0603")
      (footprint "0603")
      (description "Resistor")
      (fields (field (name "ALTIUM_VALUE") "5.1K") (field (name "PUBLISHER") "Altium Limited"))
      (libsource (lib "Miscellaneous Devices") (part "Res1"))
    )
    (comp (ref "R19")
      (value "R0603")
      (footprint "0603")
      (description "Resistor")
      (fields (field (name "ALTIUM_VALUE") "5.1K") (field (name "PUBLISHER") "Altium Limited"))
      (libsource (lib "Miscellaneous Devices") (part "Res1"))
    )
    (comp (ref "R20")
      (value "R0603")
      (footprint "0603")
      (description "Resistor")
      (fields (field (name "ALTIUM_VALUE") "10K") (field (name "PUBLISHER") "Altium Limited"))
      (libsource (lib "Miscellaneous Devices") (part "Res1"))
    )
    (comp (ref "R21")
      (value "R0603")
      (footprint "0603")
      (description "Resistor")
      (fields (field (name "ALTIUM_VALUE") "10K") (field (name "PUBLISHER") "Altium Limited"))
      (libsource (lib "Miscellaneous Devices") (part "Res1"))
    )
    (comp (ref "R22")
      (value "R0603")
      (footprint "0603")
      (description "Resistor")
      (fields (field (name "ALTIUM_VALUE") "10K") (field (name "PUBLISHER") "Altium Limited"))
      (libsource (lib "Miscellaneous Devices") (part "Res1"))
    )
    (comp (ref "R23")
      (value "R0603")
      (footprint "0603")
      (description "Resistor")
      (fields (field (name "ALTIUM_VALUE") "10R") (field (name "PUBLISHER") "Altium Limited"))
      (libsource (lib "Miscellaneous Devices") (part "Res1"))
    )
    (comp (ref "R24")
      (value "R0603")
      (footprint "0603")
      (description "Resistor")
      (fields (field (name "ALTIUM_VALUE") "10K") (field (name "PUBLISHER") "Altium Limited"))
      (libsource (lib "Miscellaneous Devices") (part "Res1"))
    )
    (comp (ref "R25")
      (value "R0603")
      (footprint "0603")
      (description "Resistor")
      (fields (field (name "ALTIUM_VALUE") "1K") (field (name "PUBLISHER") "Altium Limited"))
      (libsource (lib "Miscellaneous Devices") (part "Res1"))
    )
    (comp (ref "R26")
      (value "R0603")
      (footprint "0603")
      (description "Resistor")
      (fields (field (name "ALTIUM_VALUE") "1K") (field (name "PUBLISHER") "Altium Limited"))
      (libsource (lib "Miscellaneous Devices") (part "Res1"))
    )
    (comp (ref "R27")
      (value "R0603")
      (footprint "0603")
      (description "Resistor")
      (fields (field (name "ALTIUM_VALUE") "100K") (field (name "PUBLISHER") "Altium Limited"))
      (libsource (lib "Miscellaneous Devices") (part "Res1"))
    )
    (comp (ref "R28")
      (value "R0603")
      (footprint "0603")
      (description "Resistor")
      (fields (field (name "ALTIUM_VALUE") "10K") (field (name "PUBLISHER") "Altium Limited"))
      (libsource (lib "Miscellaneous Devices") (part "Res1"))
    )
    (comp (ref "R29")
      (value "R0603")
      (footprint "0603")
      (description "Resistor")
      (fields (field (name "ALTIUM_VALUE") "10R") (field (name "PUBLISHER") "Altium Limited"))
      (libsource (lib "Miscellaneous Devices") (part "Res1"))
    )
    (comp (ref "R30")
      (value "R0603")
      (footprint "0603")
      (description "Resistor")
      (fields (field (name "ALTIUM_VALUE") "10R") (field (name "PUBLISHER") "Altium Limited"))
      (libsource (lib "Miscellaneous Devices") (part "Res1"))
    )
    (comp (ref "R31")
      (value "R0603")
      (footprint "0603")
      (description "Resistor")
      (fields (field (name "ALTIUM_VALUE") "10K") (field (name "PUBLISHER") "Altium Limited"))
      (libsource (lib "Miscellaneous Devices") (part "Res1"))
    )
    (comp (ref "R32")
      (value "R2512")
      (footprint "R2512")
      (description "Resistor")
      (fields (field (name "ALTIUM_VALUE") "0.2R") (field (name "PUBLISHER") "Altium Limited"))
      (libsource (lib "Miscellaneous Devices") (part "Res1"))
    )
    (comp (ref "R33")
      (value "R1206")
      (footprint "1206")
      (description "Resistor")
      (fields (field (name "ALTIUM_VALUE") "N/A") (field (name "PUBLISHER") "Altium Limited"))
      (libsource (lib "Miscellaneous Devices") (part "Res1"))
    )
    (comp (ref "R34")
      (value "R0603")
      (footprint "0603")
      (description "Resistor")
      (fields (field (name "ALTIUM_VALUE") "10K") (field (name "PUBLISHER") "Altium Limited"))
      (libsource (lib "Miscellaneous Devices") (part "Res1"))
    )
    (comp (ref "R35")
      (value "R0603")
      (footprint "0603")
      (description "Resistor")
      (fields (field (name "ALTIUM_VALUE") "10K") (field (name "PUBLISHER") "Altium Limited"))
      (libsource (lib "Miscellaneous Devices") (part "Res1"))
    )
    (comp (ref "R36")
      (value "R0603")
      (footprint "0603")
      (description "Resistor")
      (fields (field (name "ALTIUM_VALUE") "10K") (field (name "PUBLISHER") "Altium Limited"))
      (libsource (lib "Miscellaneous Devices") (part "Res1"))
    )
    (comp (ref "R37")
      (value "R0603")
      (footprint "0603")
      (description "Resistor")
      (fields (field (name "ALTIUM_VALUE") "10K") (field (name "PUBLISHER") "Altium Limited"))
      (libsource (lib "Miscellaneous Devices") (part "Res1"))
    )
    (comp (ref "R38")
      (value "R0603")
      (footprint "0603")
      (description "Resistor")
      (fields (field (name "ALTIUM_VALUE") "10K") (field (name "PUBLISHER") "Altium Limited"))
      (libsource (lib "Miscellaneous Devices") (part "Res1"))
    )
    (comp (ref "R39")
      (value "R0603")
      (footprint "0603")
      (description "Resistor")
      (fields (field (name "ALTIUM_VALUE") "10K") (field (name "PUBLISHER") "Altium Limited"))
      (libsource (lib "Miscellaneous Devices") (part "Res1"))
    )
    (comp (ref "R40")
      (value "R0603")
      (footprint "0603")
      (description "Resistor")
      (fields (field (name "ALTIUM_VALUE") "10K") (field (name "PUBLISHER") "Altium Limited"))
      (libsource (lib "Miscellaneous Devices") (part "Res1"))
    )
    (comp (ref "R41")
      (value "R0603")
      (footprint "0603")
      (description "Resistor")
      (fields (field (name "ALTIUM_VALUE") "10K") (field (name "PUBLISHER") "Altium Limited"))
      (libsource (lib "Miscellaneous Devices") (part "Res1"))
    )
    (comp (ref "R42")
      (value "R0603")
      (footprint "0603")
      (description "Resistor")
      (fields (field (name "ALTIUM_VALUE") "10K") (field (name "PUBLISHER") "Altium Limited"))
      (libsource (lib "Miscellaneous Devices") (part "Res1"))
    )
    (comp (ref "R43")
      (value "R0603")
      (footprint "0603")
      (description "Resistor")
      (fields (field (name "ALTIUM_VALUE") "10K") (field (name "PUBLISHER") "Altium Limited"))
      (libsource (lib "Miscellaneous Devices") (part "Res1"))
    )
    (comp (ref "R44")
      (value "R0603")
      (footprint "0603")
      (description "Resistor")
      (fields (field (name "ALTIUM_VALUE") "10K") (field (name "PUBLISHER") "Altium Limited"))
      (libsource (lib "Miscellaneous Devices") (part "Res1"))
    )
    (comp (ref "R45")
      (value "R0603")
      (footprint "0603")
      (description "Resistor")
      (fields (field (name "ALTIUM_VALUE") "5.1K") (field (name "PUBLISHER") "Altium Limited"))
      (libsource (lib "Miscellaneous Devices") (part "Res1"))
    )
    (comp (ref "R46")
      (value "R0603")
      (footprint "0603")
      (description "Resistor")
      (fields (field (name "ALTIUM_VALUE") "5.1K") (field (name "PUBLISHER") "Altium Limited"))
      (libsource (lib "Miscellaneous Devices") (part "Res1"))
    )
    (comp (ref "R47")
      (value "R0603")
      (footprint "0603")
      (description "Resistor")
      (fields (field (name "ALTIUM_VALUE") "5.1K") (field (name "PUBLISHER") "Altium Limited"))
      (libsource (lib "Miscellaneous Devices") (part "Res1"))
    )
    (comp (ref "R48")
      (value "R0603")
      (footprint "0603")
      (description "Resistor")
      (fields (field (name "ALTIUM_VALUE") "5.1K") (field (name "PUBLISHER") "Altium Limited"))
      (libsource (lib "Miscellaneous Devices") (part "Res1"))
    )
    (comp (ref "R49")
      (value "R0603")
      (footprint "0603")
      (description "Resistor")
      (fields (field (name "ALTIUM_VALUE") "10K") (field (name "PUBLISHER") "Altium Limited"))
      (libsource (lib "Miscellaneous Devices") (part "Res1"))
    )
    (comp (ref "R50")
      (value "R0603")
      (footprint "0603")
      (description "Resistor")
      (fields (field (name "ALTIUM_VALUE") "10K") (field (name "PUBLISHER") "Altium Limited"))
      (libsource (lib "Miscellaneous Devices") (part "Res1"))
    )
    (comp (ref "R51")
      (value "R0603")
      (footprint "0603")
      (description "Resistor")
      (fields (field (name "ALTIUM_VALUE") "1K") (field (name "PUBLISHER") "Altium Limited"))
      (libsource (lib "Miscellaneous Devices") (part "Res1"))
    )
    (comp (ref "R52")
      (value "R0603")
      (footprint "0603")
      (description "Resistor")
      (fields (field (name "ALTIUM_VALUE") "1K") (field (name "PUBLISHER") "Altium Limited"))
      (libsource (lib "Miscellaneous Devices") (part "Res1"))
    )
    (comp (ref "R53")
      (value "R0603")
      (footprint "0603")
      (description "Resistor")
      (fields (field (name "ALTIUM_VALUE") "10K") (field (name "PUBLISHER") "Altium Limited"))
      (libsource (lib "Miscellaneous Devices") (part "Res1"))
    )
    (comp (ref "R54")
      (value "R0603")
      (footprint "0603")
      (description "Resistor")
      (fields (field (name "ALTIUM_VALUE") "10R") (field (name "PUBLISHER") "Altium Limited"))
      (libsource (lib "Miscellaneous Devices") (part "Res1"))
    )
    (comp (ref "R55")
      (value "R0603")
      (footprint "0603")
      (description "Resistor")
      (fields (field (name "ALTIUM_VALUE") "10R") (field (name "PUBLISHER") "Altium Limited"))
      (libsource (lib "Miscellaneous Devices") (part "Res1"))
    )
    (comp (ref "R56")
      (value "R0603")
      (footprint "0603")
      (description "Resistor")
      (fields (field (name "ALTIUM_VALUE") "10K") (field (name "PUBLISHER") "Altium Limited"))
      (libsource (lib "Miscellaneous Devices") (part "Res1"))
    )
    (comp (ref "R57")
      (value "R1206")
      (footprint "1206")
      (description "Resistor")
      (fields (field (name "ALTIUM_VALUE") "N/A") (field (name "PUBLISHER") "Altium Limited"))
      (libsource (lib "Miscellaneous Devices") (part "Res1"))
    )
    (comp (ref "R58")
      (value "R0603")
      (footprint "0603")
      (description "Resistor")
      (fields (field (name "ALTIUM_VALUE") "51K") (field (name "PUBLISHER") "Altium Limited"))
      (libsource (lib "Miscellaneous Devices") (part "Res1"))
    )
    (comp (ref "R59")
      (value "R0603")
      (footprint "0603")
      (description "Resistor")
      (fields (field (name "ALTIUM_VALUE") "10K") (field (name "PUBLISHER") "Altium Limited"))
      (libsource (lib "Miscellaneous Devices") (part "Res1"))
    )
    (comp (ref "R60")
      (value "R0603")
      (footprint "0603")
      (description "Resistor")
      (fields (field (name "ALTIUM_VALUE") "5.1K") (field (name "PUBLISHER") "Altium Limited"))
      (libsource (lib "Miscellaneous Devices") (part "Res1"))
    )
    (comp (ref "R61")
      (value "R0603")
      (footprint "0603")
      (description "Resistor")
      (fields (field (name "ALTIUM_VALUE") "5.1K") (field (name "PUBLISHER") "Altium Limited"))
      (libsource (lib "Miscellaneous Devices") (part "Res1"))
    )
    (comp (ref "R62")
      (value "R0603")
      (footprint "0603")
      (description "Resistor")
      (fields (field (name "ALTIUM_VALUE") "5.1K") (field (name "PUBLISHER") "Altium Limited"))
      (libsource (lib "Miscellaneous Devices") (part "Res1"))
    )
    (comp (ref "R63")
      (value "R0603")
      (footprint "0603")
      (description "Resistor")
      (fields (field (name "ALTIUM_VALUE") "5.1K") (field (name "PUBLISHER") "Altium Limited"))
      (libsource (lib "Miscellaneous Devices") (part "Res1"))
    )
    (comp (ref "R64")
      (value "R0603")
      (footprint "0603")
      (description "Resistor")
      (fields (field (name "ALTIUM_VALUE") "0R") (field (name "PUBLISHER") "Altium Limited"))
      (libsource (lib "Miscellaneous Devices") (part "Res1"))
    )
    (comp (ref "R65")
      (value "R0603")
      (footprint "0603")
      (description "Resistor")
      (fields (field (name "ALTIUM_VALUE") "N/A") (field (name "PUBLISHER") "Altium Limited"))
      (libsource (lib "Miscellaneous Devices") (part "Res1"))
    )
    (comp (ref "R66")
      (value "R0603")
      (footprint "0603")
      (description "Resistor")
      (fields (field (name "ALTIUM_VALUE") "5.1K") (field (name "PUBLISHER") "Altium Limited"))
      (libsource (lib "Miscellaneous Devices") (part "Res1"))
    )
    (comp (ref "R67")
      (value "R0603")
      (footprint "0603")
      (description "Resistor")
      (fields (field (name "ALTIUM_VALUE") "10K") (field (name "PUBLISHER") "Altium Limited"))
      (libsource (lib "Miscellaneous Devices") (part "Res1"))
    )
    (comp (ref "R68")
      (value "R0603")
      (footprint "0603")
      (description "Resistor")
      (fields (field (name "ALTIUM_VALUE") "10K") (field (name "PUBLISHER") "Altium Limited"))
      (libsource (lib "Miscellaneous Devices") (part "Res1"))
    )
    (comp (ref "R69")
      (value "R0603")
      (footprint "0603")
      (description "Resistor")
      (fields (field (name "ALTIUM_VALUE") "1K") (field (name "PUBLISHER") "Altium Limited"))
      (libsource (lib "Miscellaneous Devices") (part "Res1"))
    )
    (comp (ref "R70")
      (value "R0603")
      (footprint "0603")
      (description "Resistor")
      (fields (field (name "ALTIUM_VALUE") "1K") (field (name "PUBLISHER") "Altium Limited"))
      (libsource (lib "Miscellaneous Devices") (part "Res1"))
    )
    (comp (ref "R71")
      (value "R0603")
      (footprint "0603")
      (description "Resistor")
      (fields (field (name "ALTIUM_VALUE") "10K") (field (name "PUBLISHER") "Altium Limited"))
      (libsource (lib "Miscellaneous Devices") (part "Res1"))
    )
    (comp (ref "R72")
      (value "R0603")
      (footprint "0603")
      (description "Resistor")
      (fields (field (name "ALTIUM_VALUE") "10R") (field (name "PUBLISHER") "Altium Limited"))
      (libsource (lib "Miscellaneous Devices") (part "Res1"))
    )
    (comp (ref "R73")
      (value "R0603")
      (footprint "0603")
      (description "Resistor")
      (fields (field (name "ALTIUM_VALUE") "10R") (field (name "PUBLISHER") "Altium Limited"))
      (libsource (lib "Miscellaneous Devices") (part "Res1"))
    )
    (comp (ref "R74")
      (value "R0603")
      (footprint "0603")
      (description "Resistor")
      (fields (field (name "ALTIUM_VALUE") "10K") (field (name "PUBLISHER") "Altium Limited"))
      (libsource (lib "Miscellaneous Devices") (part "Res1"))
    )
    (comp (ref "R75")
      (value "R1206")
      (footprint "1206")
      (description "Resistor")
      (fields (field (name "ALTIUM_VALUE") "N/A") (field (name "PUBLISHER") "Altium Limited"))
      (libsource (lib "Miscellaneous Devices") (part "Res1"))
    )
    (comp (ref "R76")
      (value "R0603")
      (footprint "0603")
      (description "Resistor")
      (fields (field (name "ALTIUM_VALUE") "100K") (field (name "PUBLISHER") "Altium Limited"))
      (libsource (lib "Miscellaneous Devices") (part "Res1"))
    )
    (comp (ref "R77")
      (value "R2512")
      (footprint "R2512")
      (description "Resistor")
      (fields (field (name "ALTIUM_VALUE") "0.2R") (field (name "PUBLISHER") "Altium Limited"))
      (libsource (lib "Miscellaneous Devices") (part "Res1"))
    )
    (comp (ref "R78")
      (value "R0603")
      (footprint "0603")
      (description "Resistor")
      (fields (field (name "ALTIUM_VALUE") "10K") (field (name "PUBLISHER") "Altium Limited"))
      (libsource (lib "Miscellaneous Devices") (part "Res1"))
    )
    (comp (ref "R79")
      (value "R0603")
      (footprint "0603")
      (description "Resistor")
      (fields (field (name "ALTIUM_VALUE") "10K") (field (name "PUBLISHER") "Altium Limited"))
      (libsource (lib "Miscellaneous Devices") (part "Res1"))
    )
    (comp (ref "R80")
      (value "R0603")
      (footprint "0603")
      (description "Resistor")
      (fields (field (name "ALTIUM_VALUE") "10K") (field (name "PUBLISHER") "Altium Limited"))
      (libsource (lib "Miscellaneous Devices") (part "Res1"))
    )
    (comp (ref "R81")
      (value "R0603")
      (footprint "0603")
      (description "Resistor")
      (fields (field (name "ALTIUM_VALUE") "10K") (field (name "PUBLISHER") "Altium Limited"))
      (libsource (lib "Miscellaneous Devices") (part "Res1"))
    )
    (comp (ref "R82")
      (value "R0603")
      (footprint "0603")
      (description "Resistor")
      (fields (field (name "ALTIUM_VALUE") "24K") (field (name "PUBLISHER") "Altium Limited"))
      (libsource (lib "Miscellaneous Devices") (part "Res1"))
    )
    (comp (ref "R83")
      (value "R0603")
      (footprint "0603")
      (description "Resistor")
      (fields (field (name "ALTIUM_VALUE") "24K") (field (name "PUBLISHER") "Altium Limited"))
      (libsource (lib "Miscellaneous Devices") (part "Res1"))
    )
    (comp (ref "R84")
      (value "R0603")
      (footprint "0603")
      (description "Resistor")
      (fields (field (name "ALTIUM_VALUE") "1K") (field (name "PUBLISHER") "Altium Limited"))
      (libsource (lib "Miscellaneous Devices") (part "Res1"))
    )
    (comp (ref "R85")
      (value "R0603")
      (footprint "0603")
      (description "Resistor")
      (fields (field (name "ALTIUM_VALUE") "1K") (field (name "PUBLISHER") "Altium Limited"))
      (libsource (lib "Miscellaneous Devices") (part "Res1"))
    )
    (comp (ref "R86")
      (value "R1206")
      (footprint "1206")
      (description "Resistor")
      (fields (field (name "ALTIUM_VALUE") "10K") (field (name "PUBLISHER") "Altium Limited"))
      (libsource (lib "Miscellaneous Devices") (part "Res1"))
    )
    (comp (ref "R87")
      (value "R1206")
      (footprint "1206")
      (description "Resistor")
      (fields (field (name "ALTIUM_VALUE") "10K") (field (name "PUBLISHER") "Altium Limited"))
      (libsource (lib "Miscellaneous Devices") (part "Res1"))
    )
    (comp (ref "R88")
      (value "R0603")
      (footprint "0603")
      (description "Resistor")
      (fields (field (name "ALTIUM_VALUE") "5.1K") (field (name "PUBLISHER") "Altium Limited"))
      (libsource (lib "Miscellaneous Devices") (part "Res1"))
    )
    (comp (ref "R89")
      (value "R0603")
      (footprint "0603")
      (description "Resistor")
      (fields (field (name "ALTIUM_VALUE") "5.1K") (field (name "PUBLISHER") "Altium Limited"))
      (libsource (lib "Miscellaneous Devices") (part "Res1"))
    )
    (comp (ref "R90")
      (value "R0603")
      (footprint "0603")
      (description "Resistor")
      (fields (field (name "ALTIUM_VALUE") "5.1K") (field (name "PUBLISHER") "Altium Limited"))
      (libsource (lib "Miscellaneous Devices") (part "Res1"))
    )
    (comp (ref "R91")
      (value "R0603")
      (footprint "0603")
      (description "Resistor")
      (fields (field (name "ALTIUM_VALUE") "5.1K") (field (name "PUBLISHER") "Altium Limited"))
      (libsource (lib "Miscellaneous Devices") (part "Res1"))
    )
    (comp (ref "R92")
      (value "R0603")
      (footprint "0603")
      (description "Resistor")
      (fields (field (name "ALTIUM_VALUE") "51K") (field (name "PUBLISHER") "Altium Limited"))
      (libsource (lib "Miscellaneous Devices") (part "Res1"))
    )
    (comp (ref "R93")
      (value "R0603")
      (footprint "0603")
      (description "Resistor")
      (fields (field (name "ALTIUM_VALUE") "10K") (field (name "PUBLISHER") "Altium Limited"))
      (libsource (lib "Miscellaneous Devices") (part "Res1"))
    )
    (comp (ref "R94")
      (value "R0603")
      (footprint "0603")
      (description "Resistor")
      (fields (field (name "ALTIUM_VALUE") "5.1K") (field (name "PUBLISHER") "Altium Limited"))
      (libsource (lib "Miscellaneous Devices") (part "Res1"))
    )
    (comp (ref "R95")
      (value "R0603")
      (footprint "0603")
      (description "Resistor")
      (fields (field (name "ALTIUM_VALUE") "5.1K") (field (name "PUBLISHER") "Altium Limited"))
      (libsource (lib "Miscellaneous Devices") (part "Res1"))
    )
    (comp (ref "R96")
      (value "R0603")
      (footprint "0603")
      (description "Resistor")
      (fields (field (name "ALTIUM_VALUE") "5.1K") (field (name "PUBLISHER") "Altium Limited"))
      (libsource (lib "Miscellaneous Devices") (part "Res1"))
    )
    (comp (ref "R97")
      (value "R0603")
      (footprint "0603")
      (description "Resistor")
      (fields (field (name "ALTIUM_VALUE") "5.1K") (field (name "PUBLISHER") "Altium Limited"))
      (libsource (lib "Miscellaneous Devices") (part "Res1"))
    )
    (comp (ref "R98")
      (value "R0603")
      (footprint "0603")
      (description "Resistor")
      (fields (field (name "ALTIUM_VALUE") "1K") (field (name "PUBLISHER") "Altium Limited"))
      (libsource (lib "Miscellaneous Devices") (part "Res1"))
    )
    (comp (ref "R99")
      (value "R0603")
      (footprint "0603")
      (description "Resistor")
      (fields (field (name "ALTIUM_VALUE") "1K") (field (name "PUBLISHER") "Altium Limited"))
      (libsource (lib "Miscellaneous Devices") (part "Res1"))
    )
    (comp (ref "R100")
      (value "R0603")
      (footprint "0603")
      (description "Resistor")
      (fields (field (name "ALTIUM_VALUE") "1K") (field (name "PUBLISHER") "Altium Limited"))
      (libsource (lib "Miscellaneous Devices") (part "Res1"))
    )
    (comp (ref "R101")
      (value "R0603")
      (footprint "0603")
      (description "Resistor")
      (fields (field (name "ALTIUM_VALUE") "5.1K") (field (name "PUBLISHER") "Altium Limited"))
      (libsource (lib "Miscellaneous Devices") (part "Res1"))
    )
    (comp (ref "R102")
      (value "R0603")
      (footprint "0603")
      (description "Resistor")
      (fields (field (name "ALTIUM_VALUE") "1K") (field (name "PUBLISHER") "Altium Limited"))
      (libsource (lib "Miscellaneous Devices") (part "Res1"))
    )
    (comp (ref "R103")
      (value "R0603")
      (footprint "0603")
      (description "Resistor")
      (fields (field (name "ALTIUM_VALUE") "10K") (field (name "PUBLISHER") "Altium Limited"))
      (libsource (lib "Miscellaneous Devices") (part "Res1"))
    )
    (comp (ref "R104")
      (value "R0603")
      (footprint "0603")
      (description "Resistor")
      (fields (field (name "ALTIUM_VALUE") "10K") (field (name "PUBLISHER") "Altium Limited"))
      (libsource (lib "Miscellaneous Devices") (part "Res1"))
    )
    (comp (ref "R105")
      (value "R0603")
      (footprint "0603")
      (description "Resistor")
      (fields (field (name "ALTIUM_VALUE") "10K") (field (name "PUBLISHER") "Altium Limited"))
      (libsource (lib "Miscellaneous Devices") (part "Res1"))
    )
    (comp (ref "R106")
      (value "R0603")
      (footprint "0603")
      (description "Resistor")
      (fields (field (name "ALTIUM_VALUE") "10K") (field (name "PUBLISHER") "Altium Limited"))
      (libsource (lib "Miscellaneous Devices") (part "Res1"))
    )
    (comp (ref "R107")
      (value "R0603")
      (footprint "0603")
      (description "Resistor")
      (fields (field (name "ALTIUM_VALUE") "10K") (field (name "PUBLISHER") "Altium Limited"))
      (libsource (lib "Miscellaneous Devices") (part "Res1"))
    )
    (comp (ref "R108")
      (value "R0603")
      (footprint "0603")
      (description "Resistor")
      (fields (field (name "ALTIUM_VALUE") "10K") (field (name "PUBLISHER") "Altium Limited"))
      (libsource (lib "Miscellaneous Devices") (part "Res1"))
    )
    (comp (ref "R109")
      (value "R0603")
      (footprint "0603")
      (description "Resistor")
      (fields (field (name "ALTIUM_VALUE") "10K") (field (name "PUBLISHER") "Altium Limited"))
      (libsource (lib "Miscellaneous Devices") (part "Res1"))
    )
    (comp (ref "R110")
      (value "R0603")
      (footprint "0603")
      (description "Resistor")
      (fields (field (name "ALTIUM_VALUE") "10K") (field (name "PUBLISHER") "Altium Limited"))
      (libsource (lib "Miscellaneous Devices") (part "Res1"))
    )
    (comp (ref "R111")
      (value "R0603")
      (footprint "0603")
      (description "Resistor")
      (fields (field (name "ALTIUM_VALUE") "10K") (field (name "PUBLISHER") "Altium Limited"))
      (libsource (lib "Miscellaneous Devices") (part "Res1"))
    )
    (comp (ref "R112")
      (value "R0603")
      (footprint "0603")
      (description "Resistor")
      (fields (field (name "ALTIUM_VALUE") "10R") (field (name "PUBLISHER") "Altium Limited"))
      (libsource (lib "Miscellaneous Devices") (part "Res1"))
    )
    (comp (ref "R113")
      (value "R0603")
      (footprint "0603")
      (description "Resistor")
      (fields (field (name "ALTIUM_VALUE") "10R") (field (name "PUBLISHER") "Altium Limited"))
      (libsource (lib "Miscellaneous Devices") (part "Res1"))
    )
    (comp (ref "R114")
      (value "R0603")
      (footprint "0603")
      (description "Resistor")
      (fields (field (name "ALTIUM_VALUE") "10R") (field (name "PUBLISHER") "Altium Limited"))
      (libsource (lib "Miscellaneous Devices") (part "Res1"))
    )
    (comp (ref "R115")
      (value "R0603")
      (footprint "0603")
      (description "Resistor")
      (fields (field (name "ALTIUM_VALUE") "10R") (field (name "PUBLISHER") "Altium Limited"))
      (libsource (lib "Miscellaneous Devices") (part "Res1"))
    )
    (comp (ref "R116")
      (value "R0603")
      (footprint "0603")
      (description "Resistor")
      (fields (field (name "ALTIUM_VALUE") "10K") (field (name "PUBLISHER") "Altium Limited"))
      (libsource (lib "Miscellaneous Devices") (part "Res1"))
    )
    (comp (ref "R117")
      (value "R0603")
      (footprint "0603")
      (description "Resistor")
      (fields (field (name "ALTIUM_VALUE") "10K") (field (name "PUBLISHER") "Altium Limited"))
      (libsource (lib "Miscellaneous Devices") (part "Res1"))
    )
    (comp (ref "R118")
      (value "R0603")
      (footprint "0603")
      (description "Resistor")
      (fields (field (name "ALTIUM_VALUE") "10K") (field (name "PUBLISHER") "Altium Limited"))
      (libsource (lib "Miscellaneous Devices") (part "Res1"))
    )
    (comp (ref "R119")
      (value "R0603")
      (footprint "0603")
      (description "Resistor")
      (fields (field (name "ALTIUM_VALUE") "10K") (field (name "PUBLISHER") "Altium Limited"))
      (libsource (lib "Miscellaneous Devices") (part "Res1"))
    )
    (comp (ref "R120")
      (value "R2512")
      (footprint "R2512")
      (description "Resistor")
      (fields (field (name "ALTIUM_VALUE") "0.02R") (field (name "PUBLISHER") "Altium Limited"))
      (libsource (lib "Miscellaneous Devices") (part "Res1"))
    )
    (comp (ref "R121")
      (value "R2512")
      (footprint "R2512")
      (description "Resistor")
      (fields (field (name "ALTIUM_VALUE") "0.02R") (field (name "PUBLISHER") "Altium Limited"))
      (libsource (lib "Miscellaneous Devices") (part "Res1"))
    )
    (comp (ref "R122")
      (value "R0603")
      (footprint "0603")
      (description "Resistor")
      (fields (field (name "ALTIUM_VALUE") "10K") (field (name "PUBLISHER") "Altium Limited"))
      (libsource (lib "Miscellaneous Devices") (part "Res1"))
    )
    (comp (ref "R123")
      (value "R0603")
      (footprint "0603")
      (description "Resistor")
      (fields (field (name "ALTIUM_VALUE") "64.9K") (field (name "PUBLISHER") "Altium Limited"))
      (libsource (lib "Miscellaneous Devices") (part "Res1"))
    )
    (comp (ref "R124")
      (value "R0603")
      (footprint "0603")
      (description "Resistor")
      (fields (field (name "ALTIUM_VALUE") "64.9K") (field (name "PUBLISHER") "Altium Limited"))
      (libsource (lib "Miscellaneous Devices") (part "Res1"))
    )
    (comp (ref "R125")
      (value "R1206")
      (footprint "1206")
      (description "Resistor")
      (fields (field (name "ALTIUM_VALUE") "N/A") (field (name "PUBLISHER") "Altium Limited"))
      (libsource (lib "Miscellaneous Devices") (part "Res1"))
    )
    (comp (ref "R126")
      (value "R1206")
      (footprint "1206")
      (description "Resistor")
      (fields (field (name "ALTIUM_VALUE") "N/A") (field (name "PUBLISHER") "Altium Limited"))
      (libsource (lib "Miscellaneous Devices") (part "Res1"))
    )
    (comp (ref "R127")
      (value "R0603")
      (footprint "0603")
      (description "Resistor")
      (fields (field (name "ALTIUM_VALUE") "10K") (field (name "PUBLISHER") "Altium Limited"))
      (libsource (lib "Miscellaneous Devices") (part "Res1"))
    )
    (comp (ref "R128")
      (value "R0603")
      (footprint "0603")
      (description "Resistor")
      (fields (field (name "ALTIUM_VALUE") "10K") (field (name "PUBLISHER") "Altium Limited"))
      (libsource (lib "Miscellaneous Devices") (part "Res1"))
    )
    (comp (ref "R129")
      (value "R0603")
      (footprint "0603")
      (description "Resistor")
      (fields (field (name "ALTIUM_VALUE") "10K") (field (name "PUBLISHER") "Altium Limited"))
      (libsource (lib "Miscellaneous Devices") (part "Res1"))
    )
    (comp (ref "R130")
      (value "R0603")
      (footprint "0603")
      (description "Resistor")
      (fields (field (name "ALTIUM_VALUE") "10K") (field (name "PUBLISHER") "Altium Limited"))
      (libsource (lib "Miscellaneous Devices") (part "Res1"))
    )
    (comp (ref "R131")
      (value "R0603")
      (footprint "0603")
      (description "Resistor")
      (fields (field (name "ALTIUM_VALUE") "10K") (field (name "PUBLISHER") "Altium Limited"))
      (libsource (lib "Miscellaneous Devices") (part "Res1"))
    )
    (comp (ref "R132")
      (value "R0603")
      (footprint "0603")
      (description "Resistor")
      (fields (field (name "ALTIUM_VALUE") "10K") (field (name "PUBLISHER") "Altium Limited"))
      (libsource (lib "Miscellaneous Devices") (part "Res1"))
    )
    (comp (ref "R133")
      (value "R0603")
      (footprint "0603")
      (description "Resistor")
      (fields (field (name "ALTIUM_VALUE") "33K") (field (name "PUBLISHER") "Altium Limited"))
      (libsource (lib "Miscellaneous Devices") (part "Res1"))
    )
    (comp (ref "R134")
      (value "R0603")
      (footprint "0603")
      (description "Resistor")
      (fields (field (name "ALTIUM_VALUE") "33K") (field (name "PUBLISHER") "Altium Limited"))
      (libsource (lib "Miscellaneous Devices") (part "Res1"))
    )
    (comp (ref "R135")
      (value "R0603")
      (footprint "0603")
      (description "Resistor")
      (fields (field (name "ALTIUM_VALUE") "680K") (field (name "PUBLISHER") "Altium Limited"))
      (libsource (lib "Miscellaneous Devices") (part "Res1"))
    )
    (comp (ref "R136")
      (value "R0603")
      (footprint "0603")
      (description "Resistor")
      (fields (field (name "ALTIUM_VALUE") "330K") (field (name "PUBLISHER") "Altium Limited"))
      (libsource (lib "Miscellaneous Devices") (part "Res1"))
    )
    (comp (ref "R137")
      (value "R0603")
      (footprint "0603")
      (description "Resistor")
      (fields (field (name "ALTIUM_VALUE") "680K") (field (name "PUBLISHER") "Altium Limited"))
      (libsource (lib "Miscellaneous Devices") (part "Res1"))
    )
    (comp (ref "R138")
      (value "R0603")
      (footprint "0603")
      (description "Resistor")
      (fields (field (name "ALTIUM_VALUE") "330K") (field (name "PUBLISHER") "Altium Limited"))
      (libsource (lib "Miscellaneous Devices") (part "Res1"))
    )
    (comp (ref "R139")
      (value "R0603")
      (footprint "0603")
      (description "Resistor")
      (fields (field (name "ALTIUM_VALUE") "10K") (field (name "PUBLISHER") "Altium Limited"))
      (libsource (lib "Miscellaneous Devices") (part "Res1"))
    )
    (comp (ref "R140")
      (value "R0603")
      (footprint "0603")
      (description "Resistor")
      (fields (field (name "ALTIUM_VALUE") "10K") (field (name "PUBLISHER") "Altium Limited"))
      (libsource (lib "Miscellaneous Devices") (part "Res1"))
    )
    (comp (ref "R141")
      (value "R0603")
      (footprint "0603")
      (description "Resistor")
      (fields (field (name "ALTIUM_VALUE") "10K") (field (name "PUBLISHER") "Altium Limited"))
      (libsource (lib "Miscellaneous Devices") (part "Res1"))
    )
    (comp (ref "R142")
      (value "R0603")
      (footprint "0603")
      (description "Resistor")
      (fields (field (name "ALTIUM_VALUE") "10K") (field (name "PUBLISHER") "Altium Limited"))
      (libsource (lib "Miscellaneous Devices") (part "Res1"))
    )
    (comp (ref "R143")
      (value "R0603")
      (footprint "0603")
      (description "Resistor")
      (fields (field (name "ALTIUM_VALUE") "47K") (field (name "PUBLISHER") "Altium Limited"))
      (libsource (lib "Miscellaneous Devices") (part "Res1"))
    )
    (comp (ref "R144")
      (value "R0603")
      (footprint "0603")
      (description "Resistor")
      (fields (field (name "ALTIUM_VALUE") "330K") (field (name "PUBLISHER") "Altium Limited"))
      (libsource (lib "Miscellaneous Devices") (part "Res1"))
    )
    (comp (ref "R145")
      (value "R0603")
      (footprint "0603")
      (description "Resistor")
      (fields (field (name "ALTIUM_VALUE") "330K") (field (name "PUBLISHER") "Altium Limited"))
      (libsource (lib "Miscellaneous Devices") (part "Res1"))
    )
    (comp (ref "R146")
      (value "R0603")
      (footprint "0603")
      (description "Resistor")
      (fields (field (name "ALTIUM_VALUE") "24K") (field (name "PUBLISHER") "Altium Limited"))
      (libsource (lib "Miscellaneous Devices") (part "Res1"))
    )
    (comp (ref "R147")
      (value "R0603")
      (footprint "0603")
      (description "Resistor")
      (fields (field (name "ALTIUM_VALUE") "330K") (field (name "PUBLISHER") "Altium Limited"))
      (libsource (lib "Miscellaneous Devices") (part "Res1"))
    )
    (comp (ref "R148")
      (value "R0603")
      (footprint "0603")
      (description "Resistor")
      (fields (field (name "ALTIUM_VALUE") "330K") (field (name "PUBLISHER") "Altium Limited"))
      (libsource (lib "Miscellaneous Devices") (part "Res1"))
    )
    (comp (ref "U1")
      (value "SO-14")
      (footprint "SO-14")
      (description "Quadruple 2-Input Positive-AND Gate")
      (fields (field (name "ALTIUM_VALUE") "NXP 74HCT08") (field (name "PUBLISHER") "Altium Limited"))
      (libsource (lib "TI Logic Gate 1") (part "SN74AHCT08N"))
    )
    (comp (ref "U2")
      (value "SO-14")
      (footprint "SO-14")
      (description "Hex Schmitt-Trigger Inverter")
      (fields (field (name "ALTIUM_VALUE") "NXP 74HCT14") (field (name "PUBLISHER") "Altium Limited"))
      (libsource (lib "TI Logic Gate 1") (part "SN74ACT14N"))
    )
    (comp (ref "U3")
      (value "SO-8")
      (footprint "SO-8")
      (fields (field (name "ALTIUM_VALUE") "LM393A"))
      (libsource (lib "CYSchlib") (part "OP"))
    )
    (comp (ref "U4")
      (value "XC6503D331")
      (footprint "SOT23-5")
      (libsource (lib "CYSchlib") (part "XC6503Dxxx"))
    )
    (comp (ref "U5")
      (value "SO-14")
      (footprint "SO-14")
      (description "Quadruple 2-Input Positive-AND Gate")
      (fields (field (name "ALTIUM_VALUE") "NXP 74HCT08") (field (name "PUBLISHER") "Altium Limited"))
      (libsource (lib "TI Logic Gate 1") (part "SN74AHCT08N"))
    )
    (comp (ref "U6")
      (value "LQFP48_N")
      (footprint "LQFP48_N")
      (description "STM32 ARM-based 32-bit MCU with 64 Kbytes Flash, 48-pin LQFP, Industrial Temperature")
      (fields (field (name "ALTIUM_VALUE") "STM32F030C8T6") (field (name "PUBLISHER") "*"))
      (libsource (lib "ST Microcontroller 32-Bit STM32 SCH") (part "STM32F103C8T6"))
    )
    (comp (ref "U7")
      (value "SO-14")
      (footprint "SO-14")
      (description "Quadruple 2-Input Positive-AND Gate")
      (fields (field (name "ALTIUM_VALUE") "NXP 74HCT08") (field (name "PUBLISHER") "Altium Limited"))
      (libsource (lib "TI Logic Gate 1") (part "SN74AHCT08N"))
    )
    (comp (ref "U8")
      (value "SOP-20")
      (footprint "SOP-20")
      (fields (field (name "ALTIUM_VALUE") "SN74HC245NSR"))
      (libsource (lib "SCH") (part "74HC245"))
    )
    (comp (ref "U9")
      (value "SO-8")
      (footprint "SO-8")
      (fields (field (name "ALTIUM_VALUE") "LM393A"))
      (libsource (lib "CYSchlib") (part "OP"))
    )
    (comp (ref "U10")
      (value "SO-8")
      (footprint "SO-8")
      (fields (field (name "ALTIUM_VALUE") "LM393A"))
      (libsource (lib "CYSchlib") (part "OP"))
    )
    (comp (ref "U11")
      (value "SO-8")
      (footprint "SO-8")
      (fields (field (name "ALTIUM_VALUE") "LM393A"))
      (libsource (lib "CYSchlib") (part "OP"))
    )
    (comp (ref "U12")
      (value "SO-8")
      (footprint "SO-8")
      (fields (field (name "ALTIUM_VALUE") "LM393A"))
      (libsource (lib "CYSchlib") (part "OP"))
    )
    (comp (ref "U13")
      (value "SO-8")
      (footprint "SO-8")
      (fields (field (name "ALTIUM_VALUE") "LM393A"))
      (libsource (lib "CYSchlib") (part "OP"))
    )
    (comp (ref "X1")
      (value "8M")
      (footprint "HC-49SMD")
      (fields (field (name "ALTIUM_VALUE") "HC-49SMD"))
      (libsource (lib "CYSchlib") (part "XTAL"))
    )
  )
  (nets
    (net (code "1") (name "/ADC-H-IN") (class "Default")
      (node (ref "C25") (pin "1") (pinfunction "1_1") (pintype "passive"))
      (node (ref "R27") (pin "1") (pinfunction "1_1") (pintype "passive"))
      (node (ref "U10") (pin "3") (pinfunction "3_3") (pintype "passive"))
    )
    (net (code "2") (name "/ADC-HEAD") (class "Default")
      (node (ref "C53") (pin "1") (pinfunction "1_1") (pintype "passive"))
      (node (ref "R118") (pin "2") (pinfunction "2_2") (pintype "passive"))
      (node (ref "U6") (pin "19") (pinfunction "PB1_19") (pintype "bidirectional"))
    )
    (net (code "3") (name "/ADC-L") (class "Default")
      (node (ref "C61") (pin "1") (pinfunction "1_1") (pintype "passive"))
      (node (ref "R79") (pin "2") (pinfunction "2_2") (pintype "passive"))
      (node (ref "U6") (pin "10") (pinfunction "PA0-WKUP_10") (pintype "bidirectional"))
    )
    (net (code "4") (name "/ADC-L-IN") (class "Default")
      (node (ref "C51") (pin "1") (pinfunction "1_1") (pintype "passive"))
      (node (ref "R116") (pin "2") (pinfunction "2_2") (pintype "passive"))
      (node (ref "U9") (pin "3") (pinfunction "3_3") (pintype "passive"))
    )
    (net (code "5") (name "/ADC-R") (class "Default")
      (node (ref "C62") (pin "1") (pinfunction "1_1") (pintype "passive"))
      (node (ref "R81") (pin "1") (pinfunction "1_1") (pintype "passive"))
      (node (ref "U6") (pin "11") (pinfunction "PA1_11") (pintype "bidirectional"))
    )
    (net (code "6") (name "/ADC-R-IN") (class "Default")
      (node (ref "C52") (pin "1") (pinfunction "1_1") (pintype "passive"))
      (node (ref "R117") (pin "2") (pinfunction "2_2") (pintype "passive"))
      (node (ref "U9") (pin "5") (pinfunction "5_5") (pintype "passive"))
    )
    (net (code "7") (name "/ADC-W-IN") (class "Default")
      (node (ref "C44") (pin "1") (pinfunction "1_1") (pintype "passive"))
      (node (ref "R76") (pin "1") (pinfunction "1_1") (pintype "passive"))
      (node (ref "U10") (pin "5") (pinfunction "5_5") (pintype "passive"))
    )
    (net (code "8") (name "/ADC-WING") (class "Default")
      (node (ref "C54") (pin "1") (pinfunction "1_1") (pintype "passive"))
      (node (ref "R122") (pin "1") (pinfunction "1_1") (pintype "passive"))
      (node (ref "U6") (pin "18") (pinfunction "PB0_18") (pintype "bidirectional"))
    )
    (net (code "9") (name "/DIR-IO-1") (class "Default")
      (node (ref "R102") (pin "2") (pinfunction "2_2") (pintype "passive"))
      (node (ref "U1") (pin "4") (pinfunction "A_4") (pintype "input"))
      (node (ref "U2") (pin "1") (pinfunction "A_1") (pintype "input"))
      (node (ref "U6") (pin "29") (pinfunction "PA8_29") (pintype "bidirectional"))
    )
    (net (code "10") (name "/DIR-IO-2") (class "Default")
      (node (ref "R99") (pin "2") (pinfunction "2_2") (pintype "passive"))
      (node (ref "U1") (pin "12") (pinfunction "A_12") (pintype "input"))
      (node (ref "U2") (pin "3") (pinfunction "A_3") (pintype "input"))
      (node (ref "U6") (pin "39") (pinfunction "PB3_39") (pintype "bidirectional"))
    )
    (net (code "11") (name "/DIR-IO-3") (class "Default")
      (node (ref "R26") (pin "2") (pinfunction "2_2") (pintype "passive"))
      (node (ref "U2") (pin "5") (pinfunction "A_5") (pintype "input"))
      (node (ref "U5") (pin "1") (pinfunction "A_1") (pintype "input"))
      (node (ref "U6") (pin "20") (pinfunction "PB2_20") (pintype "bidirectional"))
    )
    (net (code "12") (name "/DIR-IO-4") (class "Default")
      (node (ref "R52") (pin "2") (pinfunction "2_2") (pintype "passive"))
      (node (ref "U2") (pin "9") (pinfunction "A_9") (pintype "input"))
      (node (ref "U5") (pin "12") (pinfunction "A_12") (pintype "input"))
      (node (ref "U6") (pin "21") (pinfunction "PB10_21") (pintype "bidirectional"))
    )
    (net (code "13") (name "/DIR-IO-5") (class "Default")
      (node (ref "R70") (pin "2") (pinfunction "2_2") (pintype "passive"))
      (node (ref "U2") (pin "11") (pinfunction "A_11") (pintype "input"))
      (node (ref "U6") (pin "22") (pinfunction "PB11_22") (pintype "bidirectional"))
      (node (ref "U7") (pin "1") (pinfunction "A_1") (pintype "input"))
    )
    (net (code "14") (name "/DIR1N") (class "Default")
      (node (ref "R98") (pin "1") (pinfunction "1_1") (pintype "passive"))
      (node (ref "U1") (pin "2") (pinfunction "B_2") (pintype "input"))
      (node (ref "U2") (pin "2") (pinfunction "Y_2") (pintype "output"))
    )
    (net (code "15") (name "/DIR2N") (class "Default")
      (node (ref "R100") (pin "1") (pinfunction "1_1") (pintype "passive"))
      (node (ref "U1") (pin "10") (pinfunction "B_10") (pintype "input"))
      (node (ref "U2") (pin "4") (pinfunction "Y_4") (pintype "output"))
    )
    (net (code "16") (name "/DIR3N") (class "Default")
      (node (ref "R25") (pin "1") (pinfunction "1_1") (pintype "passive"))
      (node (ref "U2") (pin "6") (pinfunction "Y_6") (pintype "output"))
      (node (ref "U5") (pin "5") (pinfunction "B_5") (pintype "input"))
    )
    (net (code "17") (name "/DIR4N") (class "Default")
      (node (ref "R51") (pin "1") (pinfunction "1_1") (pintype "passive"))
      (node (ref "U2") (pin "8") (pinfunction "Y_8") (pintype "output"))
      (node (ref "U5") (pin "10") (pinfunction "B_10") (pintype "input"))
    )
    (net (code "18") (name "/DIR5N") (class "Default")
      (node (ref "R69") (pin "1") (pinfunction "1_1") (pintype "passive"))
      (node (ref "U2") (pin "10") (pinfunction "Y_10") (pintype "output"))
      (node (ref "U7") (pin "5") (pinfunction "B_5") (pintype "input"))
    )
    (net (code "19") (name "/ENC-HEAD-A") (class "Default")
      (node (ref "C64") (pin "1") (pinfunction "1_1") (pintype "passive"))
      (node (ref "R135") (pin "1") (pinfunction "1_1") (pintype "passive"))
      (node (ref "R43") (pin "1") (pinfunction "1_1") (pintype "passive"))
      (node (ref "U3") (pin "1") (pinfunction "1_1") (pintype "passive"))
      (node (ref "U6") (pin "35") (pinfunction "PF6_35") (pintype "power_in"))
    )
    (net (code "20") (name "/ENC-HEAD-A1") (class "Default")
      (node (ref "C9") (pin "1") (pinfunction "1_1") (pintype "passive"))
      (node (ref "J2") (pin "5") (pinfunction "5_5") (pintype "passive"))
      (node (ref "R135") (pin "2") (pinfunction "2_2") (pintype "passive"))
      (node (ref "R4") (pin "1") (pinfunction "1_1") (pintype "passive"))
      (node (ref "U3") (pin "3") (pinfunction "3_3") (pintype "passive"))
    )
    (net (code "21") (name "/ENC-HEAD-B") (class "Default")
      (node (ref "C65") (pin "1") (pinfunction "1_1") (pintype "passive"))
      (node (ref "R137") (pin "1") (pinfunction "1_1") (pintype "passive"))
      (node (ref "R44") (pin "1") (pinfunction "1_1") (pintype "passive"))
      (node (ref "U3") (pin "7") (pinfunction "7_7") (pintype "passive"))
      (node (ref "U6") (pin "36") (pinfunction "PF7_36") (pintype "power_in"))
    )
    (net (code "22") (name "/ENC-HEAD-B1") (class "Default")
      (node (ref "C8") (pin "1") (pinfunction "1_1") (pintype "passive"))
      (node (ref "J2") (pin "4") (pinfunction "4_4") (pintype "passive"))
      (node (ref "R137") (pin "2") (pinfunction "2_2") (pintype "passive"))
      (node (ref "R3") (pin "1") (pinfunction "1_1") (pintype "passive"))
      (node (ref "U3") (pin "5") (pinfunction "5_5") (pintype "passive"))
    )
    (net (code "23") (name "/ENC-L-A") (class "Default")
      (node (ref "U6") (pin "33") (pinfunction "PA12_33") (pintype "bidirectional"))
      (node (ref "U8") (pin "5") (pinfunction "A3_5") (pintype "passive"))
    )
    (net (code "24") (name "/ENC-L-A-J") (class "Default")
      (node (ref "C33") (pin "1") (pinfunction "1_1") (pintype "passive"))
      (node (ref "J7") (pin "2") (pinfunction "2_2") (pintype "passive"))
      (node (ref "R37") (pin "1") (pinfunction "1_1") (pintype "passive"))
      (node (ref "U8") (pin "15") (pinfunction "B3_15") (pintype "passive"))
    )
    (net (code "25") (name "/ENC-L-B") (class "Default")
      (node (ref "U6") (pin "32") (pinfunction "PA11_32") (pintype "bidirectional"))
      (node (ref "U8") (pin "4") (pinfunction "A2_4") (pintype "passive"))
    )
    (net (code "26") (name "/ENC-L-B-J") (class "Default")
      (node (ref "C34") (pin "1") (pinfunction "1_1") (pintype "passive"))
      (node (ref "J7") (pin "3") (pinfunction "3_3") (pintype "passive"))
      (node (ref "R38") (pin "1") (pinfunction "1_1") (pintype "passive"))
      (node (ref "U8") (pin "16") (pinfunction "B2_16") (pintype "passive"))
    )
    (net (code "27") (name "/ENC-R-A") (class "Default")
      (node (ref "U6") (pin "31") (pinfunction "PA10_31") (pintype "bidirectional"))
      (node (ref "U8") (pin "3") (pinfunction "A1_3") (pintype "passive"))
    )
    (net (code "28") (name "/ENC-R-A-J") (class "Default")
      (node (ref "C36") (pin "1") (pinfunction "1_1") (pintype "passive"))
      (node (ref "J7") (pin "5") (pinfunction "5_5") (pintype "passive"))
      (node (ref "R40") (pin "1") (pinfunction "1_1") (pintype "passive"))
      (node (ref "U8") (pin "17") (pinfunction "B1_17") (pintype "passive"))
    )
    (net (code "29") (name "/ENC-R-B") (class "Default")
      (node (ref "U6") (pin "30") (pinfunction "PA9_30") (pintype "bidirectional"))
      (node (ref "U8") (pin "2") (pinfunction "A0_2") (pintype "passive"))
    )
    (net (code "30") (name "/ENC-R-B-J") (class "Default")
      (node (ref "C37") (pin "1") (pinfunction "1_1") (pintype "passive"))
      (node (ref "J7") (pin "6") (pinfunction "6_6") (pintype "passive"))
      (node (ref "R41") (pin "1") (pinfunction "1_1") (pintype "passive"))
      (node (ref "U8") (pin "18") (pinfunction "B0_18") (pintype "passive"))
    )
    (net (code "31") (name "/ENC-W-L") (class "Default")
      (node (ref "C70") (pin "1") (pinfunction "1_1") (pintype "passive"))
      (node (ref "R139") (pin "1") (pinfunction "1_1") (pintype "passive"))
      (node (ref "R144") (pin "1") (pinfunction "1_1") (pintype "passive"))
      (node (ref "U12") (pin "1") (pinfunction "1_1") (pintype "passive"))
      (node (ref "U6") (pin "40") (pinfunction "PB4_40") (pintype "bidirectional"))
    )
    (net (code "32") (name "/ENC-W-L1") (class "Default")
      (node (ref "C22") (pin "1") (pinfunction "1_1") (pintype "passive"))
      (node (ref "J3") (pin "3") (pinfunction "3_3") (pintype "passive"))
      (node (ref "R144") (pin "2") (pinfunction "2_2") (pintype "passive"))
      (node (ref "R15") (pin "1") (pinfunction "1_1") (pintype "passive"))
      (node (ref "U12") (pin "3") (pinfunction "3_3") (pintype "passive"))
    )
    (net (code "33") (name "/ENC-W-R") (class "Default")
      (node (ref "C73") (pin "1") (pinfunction "1_1") (pintype "passive"))
      (node (ref "R141") (pin "1") (pinfunction "1_1") (pintype "passive"))
      (node (ref "R145") (pin "1") (pinfunction "1_1") (pintype "passive"))
      (node (ref "U13") (pin "1") (pinfunction "1_1") (pintype "passive"))
      (node (ref "U6") (pin "41") (pinfunction "PB5_41") (pintype "bidirectional"))
    )
    (net (code "34") (name "/ENC-W-R1") (class "Default")
      (node (ref "C24") (pin "1") (pinfunction "1_1") (pintype "passive"))
      (node (ref "J4") (pin "3") (pinfunction "3_3") (pintype "passive"))
      (node (ref "R145") (pin "2") (pinfunction "2_2") (pintype "passive"))
      (node (ref "R17") (pin "1") (pinfunction "1_1") (pintype "passive"))
      (node (ref "U13") (pin "3") (pinfunction "3_3") (pintype "passive"))
    )
    (net (code "35") (name "/FAULT") (class "Default")
      (node (ref "D3") (pin "1") (pinfunction "A_1") (pintype "passive"))
      (node (ref "D4") (pin "1") (pinfunction "A_1") (pintype "passive"))
      (node (ref "Q25") (pin "3") (pinfunction "C_3") (pintype "passive"))
      (node (ref "R129") (pin "2") (pinfunction "2_2") (pintype "passive"))
      (node (ref "U6") (pin "4") (pinfunction "PC15-OSC32-OUT_4") (pintype "bidirectional"))
    )
    (net (code "36") (name "/HEAD_IO_L") (class "Default")
      (node (ref "C67") (pin "1") (pinfunction "1_1") (pintype "passive"))
      (node (ref "R132") (pin "1") (pinfunction "1_1") (pintype "passive"))
      (node (ref "R138") (pin "1") (pinfunction "1_1") (pintype "passive"))
      (node (ref "U11") (pin "7") (pinfunction "7_7") (pintype "passive"))
      (node (ref "U6") (pin "45") (pinfunction "PB8_45") (pintype "bidirectional"))
    )
    (net (code "37") (name "/HEAD_IO_L1") (class "Default")
      (node (ref "C7") (pin "1") (pinfunction "1_1") (pintype "passive"))
      (node (ref "J2") (pin "3") (pinfunction "3_3") (pintype "passive"))
      (node (ref "R138") (pin "2") (pinfunction "2_2") (pintype "passive"))
      (node (ref "R2") (pin "1") (pinfunction "1_1") (pintype "passive"))
      (node (ref "U11") (pin "5") (pinfunction "5_5") (pintype "passive"))
    )
    (net (code "38") (name "/HEAD_IO_R") (class "Default")
      (node (ref "C66") (pin "1") (pinfunction "1_1") (pintype "passive"))
      (node (ref "R131") (pin "1") (pinfunction "1_1") (pintype "passive"))
      (node (ref "R136") (pin "1") (pinfunction "1_1") (pintype "passive"))
      (node (ref "U11") (pin "1") (pinfunction "1_1") (pintype "passive"))
      (node (ref "U6") (pin "46") (pinfunction "PB9_46") (pintype "bidirectional"))
    )
    (net (code "39") (name "/HEAD_IO_R1") (class "Default")
      (node (ref "C6") (pin "1") (pinfunction "1_1") (pintype "passive"))
      (node (ref "J2") (pin "2") (pinfunction "2_2") (pintype "passive"))
      (node (ref "R1") (pin "1") (pinfunction "1_1") (pintype "passive"))
      (node (ref "R136") (pin "2") (pinfunction "2_2") (pintype "passive"))
      (node (ref "U11") (pin "3") (pinfunction "3_3") (pintype "passive"))
    )
    (net (code "40") (name "/MOT-H-A") (class "Default")
      (node (ref "C28") (pin "2") (pinfunction "2_2") (pintype "passive"))
      (node (ref "J5") (pin "1") (pinfunction "1_1") (pintype "passive"))
      (node (ref "Q1") (pin "5") (pinfunction "D_5") (pintype "passive"))
      (node (ref "R33") (pin "2") (pinfunction "2_2") (pintype "passive"))
    )
    (net (code "41") (name "/MOT-H-B") (class "Default")
      (node (ref "C28") (pin "1") (pinfunction "1_1") (pintype "passive"))
      (node (ref "J5") (pin "2") (pinfunction "2_2") (pintype "passive"))
      (node (ref "Q2") (pin "5") (pinfunction "D_5") (pintype "passive"))
      (node (ref "R33") (pin "1") (pinfunction "1_1") (pintype "passive"))
    )
    (net (code "42") (name "/MOT-L-A") (class "Default")
      (node (ref "C56") (pin "2") (pinfunction "2_2") (pintype "passive"))
      (node (ref "J8") (pin "1") (pinfunction "1_1") (pintype "passive"))
      (node (ref "Q13") (pin "3") (pinfunction "D_3") (pintype "passive"))
      (node (ref "Q18") (pin "3") (pinfunction "D_3") (pintype "passive"))
      (node (ref "R126") (pin "2") (pinfunction "2_2") (pintype "passive"))
    )
    (net (code "43") (name "/MOT-L-B") (class "Default")
      (node (ref "C56") (pin "1") (pinfunction "1_1") (pintype "passive"))
      (node (ref "J8") (pin "2") (pinfunction "2_2") (pintype "passive"))
      (node (ref "Q14") (pin "3") (pinfunction "D_3") (pintype "passive"))
      (node (ref "Q19") (pin "3") (pinfunction "D_3") (pintype "passive"))
      (node (ref "R126") (pin "1") (pinfunction "1_1") (pintype "passive"))
    )
    (net (code "44") (name "/MOT-R-A") (class "Default")
      (node (ref "C55") (pin "2") (pinfunction "2_2") (pintype "passive"))
      (node (ref "J8") (pin "3") (pinfunction "3_3") (pintype "passive"))
      (node (ref "Q16") (pin "3") (pinfunction "D_3") (pintype "passive"))
      (node (ref "Q20") (pin "3") (pinfunction "D_3") (pintype "passive"))
      (node (ref "R125") (pin "2") (pinfunction "2_2") (pintype "passive"))
    )
    (net (code "45") (name "/MOT-R-B") (class "Default")
      (node (ref "C55") (pin "1") (pinfunction "1_1") (pintype "passive"))
      (node (ref "J8") (pin "4") (pinfunction "4_4") (pintype "passive"))
      (node (ref "Q15") (pin "3") (pinfunction "D_3") (pintype "passive"))
      (node (ref "Q21") (pin "3") (pinfunction "D_3") (pintype "passive"))
      (node (ref "R125") (pin "1") (pinfunction "1_1") (pintype "passive"))
    )
    (net (code "46") (name "/MOT-STOP1") (class "Default")
      (node (ref "C32") (pin "1") (pinfunction "1_1") (pintype "passive"))
      (node (ref "J1") (pin "5") (pinfunction "5_5") (pintype "passive"))
      (node (ref "R36") (pin "2") (pinfunction "2_2") (pintype "passive"))
      (node (ref "U8") (pin "12") (pinfunction "B6_12") (pintype "passive"))
    )
    (net (code "47") (name "/MOT-W-LA") (class "Default")
      (node (ref "C42") (pin "2") (pinfunction "2_2") (pintype "passive"))
      (node (ref "J3") (pin "6") (pinfunction "6_6") (pintype "passive"))
      (node (ref "Q5") (pin "5") (pinfunction "D_5") (pintype "passive"))
      (node (ref "R57") (pin "2") (pinfunction "2_2") (pintype "passive"))
    )
    (net (code "48") (name "/MOT-W-LB") (class "Default")
      (node (ref "C42") (pin "1") (pinfunction "1_1") (pintype "passive"))
      (node (ref "J3") (pin "5") (pinfunction "5_5") (pintype "passive"))
      (node (ref "Q6") (pin "5") (pinfunction "D_5") (pintype "passive"))
      (node (ref "R57") (pin "1") (pinfunction "1_1") (pintype "passive"))
    )
    (net (code "49") (name "/MOT-W-RA") (class "Default")
      (node (ref "C45") (pin "2") (pinfunction "2_2") (pintype "passive"))
      (node (ref "J4") (pin "7") (pinfunction "7_7") (pintype "passive"))
      (node (ref "Q9") (pin "5") (pinfunction "D_5") (pintype "passive"))
      (node (ref "R75") (pin "2") (pinfunction "2_2") (pintype "passive"))
    )
    (net (code "50") (name "/MOT-W-RB") (class "Default")
      (node (ref "C45") (pin "1") (pinfunction "1_1") (pintype "passive"))
      (node (ref "J4") (pin "6") (pinfunction "6_6") (pintype "passive"))
      (node (ref "Q10") (pin "5") (pinfunction "D_5") (pintype "passive"))
      (node (ref "R75") (pin "1") (pinfunction "1_1") (pintype "passive"))
    )
    (net (code "51") (name "/PWM-1-A") (class "Default")
      (node (ref "R112") (pin "1") (pinfunction "1_1") (pintype "passive"))
      (node (ref "U1") (pin "3") (pinfunction "Y_3") (pintype "output"))
    )
    (net (code "52") (name "/PWM-1-B") (class "Default")
      (node (ref "R113") (pin "1") (pinfunction "1_1") (pintype "passive"))
      (node (ref "U1") (pin "6") (pinfunction "Y_6") (pintype "output"))
    )
    (net (code "53") (name "/PWM-2-A") (class "Default")
      (node (ref "R114") (pin "1") (pinfunction "1_1") (pintype "passive"))
      (node (ref "U1") (pin "8") (pinfunction "Y_8") (pintype "output"))
    )
    (net (code "54") (name "/PWM-2-B") (class "Default")
      (node (ref "R115") (pin "1") (pinfunction "1_1") (pintype "passive"))
      (node (ref "U1") (pin "11") (pinfunction "Y_11") (pintype "output"))
    )
    (net (code "55") (name "/PWM-3-A") (class "Default")
      (node (ref "R29") (pin "2") (pinfunction "2_2") (pintype "passive"))
      (node (ref "U5") (pin "6") (pinfunction "Y_6") (pintype "output"))
    )
    (net (code "56") (name "/PWM-3-B") (class "Default")
      (node (ref "R30") (pin "2") (pinfunction "2_2") (pintype "passive"))
      (node (ref "U5") (pin "3") (pinfunction "Y_3") (pintype "output"))
    )
    (net (code "57") (name "/PWM-4-A") (class "Default")
      (node (ref "R54") (pin "2") (pinfunction "2_2") (pintype "passive"))
      (node (ref "U5") (pin "8") (pinfunction "Y_8") (pintype "output"))
    )
    (net (code "58") (name "/PWM-4-B") (class "Default")
      (node (ref "R55") (pin "2") (pinfunction "2_2") (pintype "passive"))
      (node (ref "U5") (pin "11") (pinfunction "Y_11") (pintype "output"))
    )
    (net (code "59") (name "/PWM-5-A") (class "Default")
      (node (ref "R72") (pin "2") (pinfunction "2_2") (pintype "passive"))
      (node (ref "U7") (pin "6") (pinfunction "Y_6") (pintype "output"))
    )
    (net (code "60") (name "/PWM-5-B") (class "Default")
      (node (ref "R73") (pin "2") (pinfunction "2_2") (pintype "passive"))
      (node (ref "U7") (pin "3") (pinfunction "Y_3") (pintype "output"))
    )
    (net (code "61") (name "/PWM-IO-1") (class "Default")
      (node (ref "R8") (pin "1") (pinfunction "1_1") (pintype "passive"))
      (node (ref "U1") (pin "1") (pinfunction "A_1") (pintype "input"))
      (node (ref "U1") (pin "5") (pinfunction "B_5") (pintype "input"))
      (node (ref "U6") (pin "12") (pinfunction "PA2_12") (pintype "bidirectional"))
    )
    (net (code "62") (name "/PWM-IO-2") (class "Default")
      (node (ref "R11") (pin "1") (pinfunction "1_1") (pintype "passive"))
      (node (ref "U1") (pin "13") (pinfunction "B_13") (pintype "input"))
      (node (ref "U1") (pin "9") (pinfunction "A_9") (pintype "input"))
      (node (ref "U6") (pin "13") (pinfunction "PA3_13") (pintype "bidirectional"))
    )
    (net (code "63") (name "/PWM-IO-3") (class "Default")
      (node (ref "R13") (pin "1") (pinfunction "1_1") (pintype "passive"))
      (node (ref "U5") (pin "2") (pinfunction "B_2") (pintype "input"))
      (node (ref "U5") (pin "4") (pinfunction "A_4") (pintype "input"))
      (node (ref "U6") (pin "14") (pinfunction "PA4_14") (pintype "bidirectional"))
    )
    (net (code "64") (name "/PWM-IO-4") (class "Default")
      (node (ref "R20") (pin "1") (pinfunction "1_1") (pintype "passive"))
      (node (ref "U5") (pin "13") (pinfunction "B_13") (pintype "input"))
      (node (ref "U5") (pin "9") (pinfunction "A_9") (pintype "input"))
      (node (ref "U6") (pin "16") (pinfunction "PA6_16") (pintype "bidirectional"))
    )
    (net (code "65") (name "/PWM-IO-5") (class "Default")
      (node (ref "R24") (pin "1") (pinfunction "1_1") (pintype "passive"))
      (node (ref "U6") (pin "17") (pinfunction "PA7_17") (pintype "bidirectional"))
      (node (ref "U7") (pin "2") (pinfunction "B_2") (pintype "input"))
      (node (ref "U7") (pin "4") (pinfunction "A_4") (pintype "input"))
    )
    (net (code "66") (name "/Ref-Head") (class "Default")
      (node (ref "C68") (pin "1") (pinfunction "1_1") (pintype "passive"))
      (node (ref "R133") (pin "1") (pinfunction "1_1") (pintype "passive"))
      (node (ref "R134") (pin "2") (pinfunction "2_2") (pintype "passive"))
      (node (ref "U11") (pin "2") (pinfunction "2_2") (pintype "passive"))
      (node (ref "U11") (pin "6") (pinfunction "6_6") (pintype "passive"))
      (node (ref "U3") (pin "2") (pinfunction "2_2") (pintype "passive"))
      (node (ref "U3") (pin "6") (pinfunction "6_6") (pintype "passive"))
    )
    (net (code "67") (name "/Ref-Wing") (class "Default")
      (node (ref "C75") (pin "1") (pinfunction "1_1") (pintype "passive"))
      (node (ref "R143") (pin "1") (pinfunction "1_1") (pintype "passive"))
      (node (ref "R146") (pin "2") (pinfunction "2_2") (pintype "passive"))
      (node (ref "U12") (pin "2") (pinfunction "2_2") (pintype "passive"))
      (node (ref "U12") (pin "6") (pinfunction "6_6") (pintype "passive"))
      (node (ref "U13") (pin "2") (pinfunction "2_2") (pintype "passive"))
      (node (ref "U13") (pin "6") (pinfunction "6_6") (pintype "passive"))
    )
    (net (code "68") (name "/SEN1") (class "Default")
      (node (ref "D2") (pin "1") (pinfunction "A_1") (pintype "passive"))
      (node (ref "R59") (pin "1") (pinfunction "1_1") (pintype "passive"))
      (node (ref "U6") (pin "27") (pinfunction "PB14_27") (pintype "bidirectional"))
    )
    (net (code "69") (name "/SEN2") (class "Default")
      (node (ref "D5") (pin "1") (pinfunction "A_1") (pintype "passive"))
      (node (ref "R93") (pin "1") (pinfunction "1_1") (pintype "passive"))
      (node (ref "U6") (pin "26") (pinfunction "PB13_26") (pintype "bidirectional"))
    )
    (net (code "70") (name "/SWCLK") (class "Default")
      (node (ref "J6") (pin "3") (pinfunction "3_3") (pintype "passive"))
      (node (ref "U6") (pin "37") (pinfunction "PA14/JTCK/SWCLK_37") (pintype "bidirectional"))
    )
    (net (code "71") (name "/SWDIO") (class "Default")
      (node (ref "J6") (pin "2") (pinfunction "2_2") (pintype "passive"))
      (node (ref "U6") (pin "34") (pinfunction "PA13/JTMS/SWDIO_34") (pintype "bidirectional"))
    )
    (net (code "72") (name "/UART1RX") (class "Default")
      (node (ref "R23") (pin "1") (pinfunction "1_1") (pintype "passive"))
      (node (ref "U6") (pin "43") (pinfunction "PB7_43") (pintype "bidirectional"))
    )
    (net (code "73") (name "/UART1RX-J") (class "Default")
      (node (ref "D1") (pin "2") (pinfunction "2_2") (pintype "passive"))
      (node (ref "J1") (pin "6") (pinfunction "6_6") (pintype "passive"))
      (node (ref "R23") (pin "2") (pinfunction "2_2") (pintype "passive"))
    )
    (net (code "74") (name "/UART1TX") (class "Default")
      (node (ref "R12") (pin "1") (pinfunction "1_1") (pintype "passive"))
      (node (ref "U6") (pin "42") (pinfunction "PB6_42") (pintype "bidirectional"))
    )
    (net (code "75") (name "/UART1TX-J") (class "Default")
      (node (ref "D1") (pin "1") (pinfunction "1_1") (pintype "passive"))
      (node (ref "J1") (pin "7") (pinfunction "7_7") (pintype "passive"))
      (node (ref "R12") (pin "2") (pinfunction "2_2") (pintype "passive"))
    )
    (net (code "76") (name "/WHEEL-Float-L") (class "Default")
      (node (ref "D4") (pin "2") (pinfunction "K_2") (pintype "passive"))
      (node (ref "U6") (pin "3") (pinfunction "PC14-OSC32-IN_3") (pintype "bidirectional"))
      (node (ref "U8") (pin "6") (pinfunction "A4_6") (pintype "passive"))
    )
    (net (code "77") (name "/WHEEL-Float-L1") (class "Default")
      (node (ref "C35") (pin "1") (pinfunction "1_1") (pintype "passive"))
      (node (ref "J7") (pin "4") (pinfunction "4_4") (pintype "passive"))
      (node (ref "R39") (pin "1") (pinfunction "1_1") (pintype "passive"))
      (node (ref "U8") (pin "14") (pinfunction "B4_14") (pintype "passive"))
    )
    (net (code "78") (name "/WHEEL-Float-R") (class "Default")
      (node (ref "D3") (pin "2") (pinfunction "K_2") (pintype "passive"))
      (node (ref "U6") (pin "2") (pinfunction "PC13-TAMPER-RTC_2") (pintype "bidirectional"))
      (node (ref "U8") (pin "7") (pinfunction "A5_7") (pintype "passive"))
    )
    (net (code "79") (name "/WHEEL-Float-R1") (class "Default")
      (node (ref "C38") (pin "1") (pinfunction "1_1") (pintype "passive"))
      (node (ref "J7") (pin "7") (pinfunction "7_7") (pintype "passive"))
      (node (ref "R42") (pin "1") (pinfunction "1_1") (pintype "passive"))
      (node (ref "U8") (pin "13") (pinfunction "B5_13") (pintype "passive"))
    )
    (net (code "80") (name "/W_IO_L") (class "Default")
      (node (ref "C71") (pin "1") (pinfunction "1_1") (pintype "passive"))
      (node (ref "R140") (pin "1") (pinfunction "1_1") (pintype "passive"))
      (node (ref "R147") (pin "1") (pinfunction "1_1") (pintype "passive"))
      (node (ref "U12") (pin "7") (pinfunction "7_7") (pintype "passive"))
      (node (ref "U6") (pin "28") (pinfunction "PB15_28") (pintype "bidirectional"))
    )
    (net (code "81") (name "/W_IO_L1") (class "Default")
      (node (ref "C21") (pin "1") (pinfunction "1_1") (pintype "passive"))
      (node (ref "J3") (pin "2") (pinfunction "2_2") (pintype "passive"))
      (node (ref "R14") (pin "1") (pinfunction "1_1") (pintype "passive"))
      (node (ref "R147") (pin "2") (pinfunction "2_2") (pintype "passive"))
      (node (ref "U12") (pin "5") (pinfunction "5_5") (pintype "passive"))
    )
    (net (code "82") (name "/W_IO_R") (class "Default")
      (node (ref "C74") (pin "1") (pinfunction "1_1") (pintype "passive"))
      (node (ref "R142") (pin "1") (pinfunction "1_1") (pintype "passive"))
      (node (ref "R148") (pin "1") (pinfunction "1_1") (pintype "passive"))
      (node (ref "U13") (pin "7") (pinfunction "7_7") (pintype "passive"))
      (node (ref "U6") (pin "38") (pinfunction "PA15/JTDI_38") (pintype "bidirectional"))
    )
    (net (code "83") (name "/W_IO_R1") (class "Default")
      (node (ref "C23") (pin "1") (pinfunction "1_1") (pintype "passive"))
      (node (ref "J4") (pin "2") (pinfunction "2_2") (pintype "passive"))
      (node (ref "R148") (pin "2") (pinfunction "2_2") (pintype "passive"))
      (node (ref "R16") (pin "1") (pinfunction "1_1") (pintype "passive"))
      (node (ref "U13") (pin "5") (pinfunction "5_5") (pintype "passive"))
    )
    (net (code "84") (name "3.3V") (class "Default")
      (node (ref "C15") (pin "1") (pinfunction "1_1") (pintype "passive"))
      (node (ref "C16") (pin "2") (pinfunction "2_2") (pintype "passive"))
      (node (ref "C17") (pin "2") (pinfunction "2_2") (pintype "passive"))
      (node (ref "C19") (pin "1") (pinfunction "1_1") (pintype "passive"))
      (node (ref "C30") (pin "1") (pinfunction "1_1") (pintype "passive"))
      (node (ref "C31") (pin "1") (pinfunction "1_1") (pintype "passive"))
      (node (ref "C41") (pin "1") (pinfunction "1_1") (pintype "passive"))
      (node (ref "C46") (pin "1") (pinfunction "1_1") (pintype "passive"))
      (node (ref "C50") (pin "1") (pinfunction "1_1") (pintype "passive"))
      (node (ref "D2") (pin "2") (pinfunction "K_2") (pintype "passive"))
      (node (ref "D5") (pin "2") (pinfunction "K_2") (pintype "passive"))
      (node (ref "J6") (pin "1") (pinfunction "1_1") (pintype "passive"))
      (node (ref "R111") (pin "2") (pinfunction "2_2") (pintype "passive"))
      (node (ref "R119") (pin "2") (pinfunction "2_2") (pintype "passive"))
      (node (ref "R129") (pin "1") (pinfunction "1_1") (pintype "passive"))
      (node (ref "R131") (pin "2") (pinfunction "2_2") (pintype "passive"))
      (node (ref "R132") (pin "2") (pinfunction "2_2") (pintype "passive"))
      (node (ref "R133") (pin "2") (pinfunction "2_2") (pintype "passive"))
      (node (ref "R139") (pin "2") (pinfunction "2_2") (pintype "passive"))
      (node (ref "R140") (pin "2") (pinfunction "2_2") (pintype "passive"))
      (node (ref "R141") (pin "2") (pinfunction "2_2") (pintype "passive"))
      (node (ref "R142") (pin "2") (pinfunction "2_2") (pintype "passive"))
      (node (ref "R143") (pin "2") (pinfunction "2_2") (pintype "passive"))
      (node (ref "R35") (pin "2") (pinfunction "2_2") (pintype "passive"))
      (node (ref "R37") (pin "2") (pinfunction "2_2") (pintype "passive"))
      (node (ref "R38") (pin "2") (pinfunction "2_2") (pintype "passive"))
      (node (ref "R39") (pin "2") (pinfunction "2_2") (pintype "passive"))
      (node (ref "R40") (pin "2") (pinfunction "2_2") (pintype "passive"))
      (node (ref "R41") (pin "2") (pinfunction "2_2") (pintype "passive"))
      (node (ref "R42") (pin "2") (pinfunction "2_2") (pintype "passive"))
      (node (ref "R43") (pin "2") (pinfunction "2_2") (pintype "passive"))
      (node (ref "R44") (pin "2") (pinfunction "2_2") (pintype "passive"))
      (node (ref "R5") (pin "2") (pinfunction "2_2") (pintype "passive"))
      (node (ref "R64") (pin "2") (pinfunction "2_2") (pintype "passive"))
      (node (ref "R78") (pin "1") (pinfunction "1_1") (pintype "passive"))
      (node (ref "R80") (pin "1") (pinfunction "1_1") (pintype "passive"))
      (node (ref "U10") (pin "8") (pinfunction "VCC_8") (pintype "passive"))
      (node (ref "U4") (pin "5") (pinfunction "OUT_5") (pintype "passive"))
      (node (ref "U6") (pin "1") (pinfunction "VDD_1") (pintype "power_in"))
      (node (ref "U6") (pin "24") (pinfunction "VDD-1_24") (pintype "power_in"))
      (node (ref "U6") (pin "48") (pinfunction "VDD-3_48") (pintype "power_in"))
      (node (ref "U6") (pin "9") (pinfunction "VDDA_9") (pintype "power_in"))
      (node (ref "U8") (pin "20") (pinfunction "VCC_20") (pintype "passive"))
      (node (ref "U9") (pin "8") (pinfunction "VCC_8") (pintype "passive"))
    )
    (net (code "85") (name "24V") (class "Default")
      (node (ref "C1") (pin "1") (pinfunction "1_1") (pintype "passive"))
      (node (ref "C3") (pin "1") (pinfunction "1_1") (pintype "passive"))
      (node (ref "C47") (pin "1") (pinfunction "1_1") (pintype "passive"))
      (node (ref "C48") (pin "1") (pinfunction "1_1") (pintype "passive"))
      (node (ref "F1") (pin "1") (pinfunction "1_1") (pintype "passive"))
      (node (ref "Q13") (pin "2") (pinfunction "S_2") (pintype "passive"))
      (node (ref "Q14") (pin "2") (pinfunction "S_2") (pintype "passive"))
      (node (ref "Q15") (pin "2") (pinfunction "S_2") (pintype "passive"))
      (node (ref "Q16") (pin "2") (pinfunction "S_2") (pintype "passive"))
      (node (ref "R86") (pin "2") (pinfunction "2_2") (pintype "passive"))
      (node (ref "R87") (pin "2") (pinfunction "2_2") (pintype "passive"))
      (node (ref "R88") (pin "2") (pinfunction "2_2") (pintype "passive"))
      (node (ref "R89") (pin "2") (pinfunction "2_2") (pintype "passive"))
      (node (ref "R90") (pin "2") (pinfunction "2_2") (pintype "passive"))
      (node (ref "R91") (pin "2") (pinfunction "2_2") (pintype "passive"))
      (node (ref "R92") (pin "2") (pinfunction "2_2") (pintype "passive"))
    )
    (net (code "86") (name "GND") (class "Default")
      (node (ref "C1") (pin "2") (pinfunction "2_2") (pintype "passive"))
      (node (ref "C10") (pin "2") (pinfunction "2_2") (pintype "passive"))
      (node (ref "C11") (pin "1") (pinfunction "1_1") (pintype "passive"))
      (node (ref "C12") (pin "1") (pinfunction "1_1") (pintype "passive"))
      (node (ref "C13") (pin "1") (pinfunction "1_1") (pintype "passive"))
      (node (ref "C14") (pin "1") (pinfunction "1_1") (pintype "passive"))
      (node (ref "C15") (pin "2") (pinfunction "2_2") (pintype "passive"))
      (node (ref "C16") (pin "1") (pinfunction "1_1") (pintype "passive"))
      (node (ref "C17") (pin "1") (pinfunction "1_1") (pintype "passive"))
      (node (ref "C18") (pin "2") (pinfunction "2_2") (pintype "passive"))
      (node (ref "C19") (pin "2") (pinfunction "2_2") (pintype "passive"))
      (node (ref "C2") (pin "2") (pinfunction "2_2") (pintype "passive"))
      (node (ref "C20") (pin "1") (pinfunction "1_1") (pintype "passive"))
      (node (ref "C21") (pin "2") (pinfunction "2_2") (pintype "passive"))
      (node (ref "C22") (pin "2") (pinfunction "2_2") (pintype "passive"))
      (node (ref "C23") (pin "2") (pinfunction "2_2") (pintype "passive"))
      (node (ref "C24") (pin "2") (pinfunction "2_2") (pintype "passive"))
      (node (ref "C25") (pin "2") (pinfunction "2_2") (pintype "passive"))
      (node (ref "C26") (pin "1") (pinfunction "1_1") (pintype "passive"))
      (node (ref "C27") (pin "1") (pinfunction "1_1") (pintype "passive"))
      (node (ref "C29") (pin "1") (pinfunction "1_1") (pintype "passive"))
      (node (ref "C3") (pin "2") (pinfunction "2_2") (pintype "passive"))
      (node (ref "C30") (pin "2") (pinfunction "2_2") (pintype "passive"))
      (node (ref "C31") (pin "2") (pinfunction "2_2") (pintype "passive"))
      (node (ref "C32") (pin "2") (pinfunction "2_2") (pintype "passive"))
      (node (ref "C33") (pin "2") (pinfunction "2_2") (pintype "passive"))
      (node (ref "C34") (pin "2") (pinfunction "2_2") (pintype "passive"))
      (node (ref "C35") (pin "2") (pinfunction "2_2") (pintype "passive"))
      (node (ref "C36") (pin "2") (pinfunction "2_2") (pintype "passive"))
      (node (ref "C37") (pin "2") (pinfunction "2_2") (pintype "passive"))
      (node (ref "C38") (pin "2") (pinfunction "2_2") (pintype "passive"))
      (node (ref "C39") (pin "2") (pinfunction "2_2") (pintype "passive"))
      (node (ref "C4") (pin "2") (pinfunction "2_2") (pintype "passive"))
      (node (ref "C40") (pin "2") (pinfunction "2_2") (pintype "passive"))
      (node (ref "C41") (pin "2") (pinfunction "2_2") (pintype "passive"))
      (node (ref "C43") (pin "2") (pinfunction "2_2") (pintype "passive"))
      (node (ref "C44") (pin "2") (pinfunction "2_2") (pintype "passive"))
      (node (ref "C46") (pin "2") (pinfunction "2_2") (pintype "passive"))
      (node (ref "C47") (pin "2") (pinfunction "2_2") (pintype "passive"))
      (node (ref "C48") (pin "2") (pinfunction "2_2") (pintype "passive"))
      (node (ref "C49") (pin "2") (pinfunction "2_2") (pintype "passive"))
      (node (ref "C5") (pin "2") (pinfunction "2_2") (pintype "passive"))
      (node (ref "C50") (pin "2") (pinfunction "2_2") (pintype "passive"))
      (node (ref "C51") (pin "2") (pinfunction "2_2") (pintype "passive"))
      (node (ref "C52") (pin "2") (pinfunction "2_2") (pintype "passive"))
      (node (ref "C53") (pin "2") (pinfunction "2_2") (pintype "passive"))
      (node (ref "C54") (pin "2") (pinfunction "2_2") (pintype "passive"))
      (node (ref "C57") (pin "2") (pinfunction "2_2") (pintype "passive"))
      (node (ref "C58") (pin "2") (pinfunction "2_2") (pintype "passive"))
      (node (ref "C59") (pin "2") (pinfunction "2_2") (pintype "passive"))
      (node (ref "C6") (pin "2") (pinfunction "2_2") (pintype "passive"))
      (node (ref "C60") (pin "2") (pinfunction "2_2") (pintype "passive"))
      (node (ref "C61") (pin "2") (pinfunction "2_2") (pintype "passive"))
      (node (ref "C62") (pin "2") (pinfunction "2_2") (pintype "passive"))
      (node (ref "C63") (pin "1") (pinfunction "1_1") (pintype "passive"))
      (node (ref "C64") (pin "2") (pinfunction "2_2") (pintype "passive"))
      (node (ref "C65") (pin "2") (pinfunction "2_2") (pintype "passive"))
      (node (ref "C66") (pin "2") (pinfunction "2_2") (pintype "passive"))
      (node (ref "C67") (pin "2") (pinfunction "2_2") (pintype "passive"))
      (node (ref "C68") (pin "2") (pinfunction "2_2") (pintype "passive"))
      (node (ref "C69") (pin "1") (pinfunction "1_1") (pintype "passive"))
      (node (ref "C7") (pin "2") (pinfunction "2_2") (pintype "passive"))
      (node (ref "C70") (pin "2") (pinfunction "2_2") (pintype "passive"))
      (node (ref "C71") (pin "2") (pinfunction "2_2") (pintype "passive"))
      (node (ref "C72") (pin "1") (pinfunction "1_1") (pintype "passive"))
      (node (ref "C73") (pin "2") (pinfunction "2_2") (pintype "passive"))
      (node (ref "C74") (pin "2") (pinfunction "2_2") (pintype "passive"))
      (node (ref "C75") (pin "2") (pinfunction "2_2") (pintype "passive"))
      (node (ref "C8") (pin "2") (pinfunction "2_2") (pintype "passive"))
      (node (ref "C9") (pin "2") (pinfunction "2_2") (pintype "passive"))
      (node (ref "D1") (pin "3") (pintype "passive"))
      (node (ref "D6") (pin "1") (pinfunction "A_1") (pintype "passive"))
      (node (ref "D7") (pin "1") (pinfunction "A_1") (pintype "passive"))
      (node (ref "J1") (pin "3") (pinfunction "3_3") (pintype "passive"))
      (node (ref "J1") (pin "4") (pinfunction "4_4") (pintype "passive"))
      (node (ref "J2") (pin "1") (pinfunction "1_1") (pintype "passive"))
      (node (ref "J3") (pin "4") (pinfunction "4_4") (pintype "passive"))
      (node (ref "J4") (pin "4") (pinfunction "4_4") (pintype "passive"))
      (node (ref "J6") (pin "4") (pinfunction "4_4") (pintype "passive"))
      (node (ref "J7") (pin "1") (pinfunction "1_1") (pintype "passive"))
      (node (ref "J9") (pin "4") (pinfunction "4_4") (pintype "passive"))
      (node (ref "Q11") (pin "2") (pinfunction "E_2") (pintype "passive"))
      (node (ref "Q12") (pin "2") (pinfunction "E_2") (pintype "passive"))
      (node (ref "Q17") (pin "2") (pinfunction "E_2") (pintype "passive"))
      (node (ref "Q22") (pin "2") (pinfunction "E_2") (pintype "passive"))
      (node (ref "Q23") (pin "2") (pinfunction "E_2") (pintype "passive"))
      (node (ref "Q24") (pin "2") (pinfunction "E_2") (pintype "passive"))
      (node (ref "Q25") (pin "2") (pinfunction "E_2") (pintype "passive"))
      (node (ref "Q3") (pin "2") (pinfunction "E_2") (pintype "passive"))
      (node (ref "Q4") (pin "2") (pinfunction "E_2") (pintype "passive"))
      (node (ref "Q7") (pin "2") (pinfunction "E_2") (pintype "passive"))
      (node (ref "Q8") (pin "2") (pinfunction "E_2") (pintype "passive"))
      (node (ref "R101") (pin "1") (pinfunction "1_1") (pintype "passive"))
      (node (ref "R103") (pin "1") (pinfunction "1_1") (pintype "passive"))
      (node (ref "R106") (pin "1") (pinfunction "1_1") (pintype "passive"))
      (node (ref "R109") (pin "1") (pinfunction "1_1") (pintype "passive"))
      (node (ref "R11") (pin "2") (pinfunction "2_2") (pintype "passive"))
      (node (ref "R110") (pin "1") (pinfunction "1_1") (pintype "passive"))
      (node (ref "R120") (pin "2") (pinfunction "2_2") (pintype "passive"))
      (node (ref "R121") (pin "2") (pinfunction "2_2") (pintype "passive"))
      (node (ref "R127") (pin "1") (pinfunction "1_1") (pintype "passive"))
      (node (ref "R128") (pin "1") (pinfunction "1_1") (pintype "passive"))
      (node (ref "R13") (pin "2") (pinfunction "2_2") (pintype "passive"))
      (node (ref "R134") (pin "1") (pinfunction "1_1") (pintype "passive"))
      (node (ref "R146") (pin "1") (pinfunction "1_1") (pintype "passive"))
      (node (ref "R20") (pin "2") (pinfunction "2_2") (pintype "passive"))
      (node (ref "R24") (pin "2") (pinfunction "2_2") (pintype "passive"))
      (node (ref "R28") (pin "1") (pinfunction "1_1") (pintype "passive"))
      (node (ref "R31") (pin "2") (pinfunction "2_2") (pintype "passive"))
      (node (ref "R32") (pin "2") (pinfunction "2_2") (pintype "passive"))
      (node (ref "R34") (pin "1") (pinfunction "1_1") (pintype "passive"))
      (node (ref "R36") (pin "1") (pinfunction "1_1") (pintype "passive"))
      (node (ref "R5") (pin "1") (pinfunction "1_1") (pintype "passive"))
      (node (ref "R53") (pin "1") (pinfunction "1_1") (pintype "passive"))
      (node (ref "R56") (pin "1") (pinfunction "1_1") (pintype "passive"))
      (node (ref "R6") (pin "1") (pinfunction "1_1") (pintype "passive"))
      (node (ref "R62") (pin "1") (pinfunction "1_1") (pintype "passive"))
      (node (ref "R7") (pin "1") (pinfunction "1_1") (pintype "passive"))
      (node (ref "R71") (pin "1") (pinfunction "1_1") (pintype "passive"))
      (node (ref "R74") (pin "1") (pinfunction "1_1") (pintype "passive"))
      (node (ref "R77") (pin "2") (pinfunction "2_2") (pintype "passive"))
      (node (ref "R8") (pin "2") (pinfunction "2_2") (pintype "passive"))
      (node (ref "R84") (pin "2") (pinfunction "2_2") (pintype "passive"))
      (node (ref "R85") (pin "2") (pinfunction "2_2") (pintype "passive"))
      (node (ref "R86") (pin "1") (pinfunction "1_1") (pintype "passive"))
      (node (ref "R87") (pin "1") (pinfunction "1_1") (pintype "passive"))
      (node (ref "U1") (pin "7") (pinfunction "GND_7") (pintype "power_in"))
      (node (ref "U10") (pin "4") (pinfunction "GND_4") (pintype "passive"))
      (node (ref "U11") (pin "4") (pinfunction "GND_4") (pintype "passive"))
      (node (ref "U12") (pin "4") (pinfunction "GND_4") (pintype "passive"))
      (node (ref "U13") (pin "4") (pinfunction "GND_4") (pintype "passive"))
      (node (ref "U2") (pin "7") (pinfunction "GND_7") (pintype "power_in"))
      (node (ref "U3") (pin "4") (pinfunction "GND_4") (pintype "passive"))
      (node (ref "U4") (pin "2") (pinfunction "GND_2") (pintype "passive"))
      (node (ref "U5") (pin "7") (pinfunction "GND_7") (pintype "power_in"))
      (node (ref "U6") (pin "23") (pinfunction "VSS-1_23") (pintype "power_in"))
      (node (ref "U6") (pin "47") (pinfunction "VSS-3_47") (pintype "power_in"))
      (node (ref "U6") (pin "8") (pinfunction "VSSA_8") (pintype "power_in"))
      (node (ref "U7") (pin "7") (pinfunction "GND_7") (pintype "power_in"))
      (node (ref "U8") (pin "1") (pinfunction "DIR_1") (pintype "passive"))
      (node (ref "U8") (pin "10") (pinfunction "GND_10") (pintype "passive"))
      (node (ref "U8") (pin "11") (pinfunction "B7_11") (pintype "passive"))
      (node (ref "U8") (pin "19") (pinfunction "~{OE}_19") (pintype "passive"))
      (node (ref "U9") (pin "4") (pinfunction "GND_4") (pintype "passive"))
    )
    (net (code "87") (name "Net-(C43-Pad1)") (class "Default")
      (node (ref "C43") (pin "1") (pinfunction "1_1") (pintype "passive"))
      (node (ref "R58") (pin "1") (pinfunction "1_1") (pintype "passive"))
      (node (ref "R59") (pin "2") (pinfunction "2_2") (pintype "passive"))
      (node (ref "R62") (pin "2") (pinfunction "2_2") (pintype "passive"))
    )
    (net (code "88") (name "Net-(C49-Pad1)") (class "Default")
      (node (ref "C49") (pin "1") (pinfunction "1_1") (pintype "passive"))
      (node (ref "R101") (pin "2") (pinfunction "2_2") (pintype "passive"))
      (node (ref "R92") (pin "1") (pinfunction "1_1") (pintype "passive"))
      (node (ref "R93") (pin "2") (pinfunction "2_2") (pintype "passive"))
    )
    (net (code "89") (name "Net-(C59-Pad1)") (class "Default")
      (node (ref "C59") (pin "1") (pinfunction "1_1") (pintype "passive"))
      (node (ref "J7") (pin "8") (pinfunction "8_8") (pintype "passive"))
      (node (ref "R64") (pin "1") (pinfunction "1_1") (pintype "passive"))
      (node (ref "R65") (pin "1") (pinfunction "1_1") (pintype "passive"))
    )
    (net (code "90") (name "Net-(D8-A)") (class "Default")
      (node (ref "D8") (pin "1") (pinfunction "A_1") (pintype "passive"))
      (node (ref "F2") (pin "1") (pinfunction "1_1") (pintype "passive"))
    )
    (net (code "91") (name "Net-(Q1-NG1)") (class "Default")
      (node (ref "Q1") (pin "2") (pinfunction "NG1_2") (pintype "passive"))
      (node (ref "R22") (pin "1") (pinfunction "1_1") (pintype "passive"))
      (node (ref "R29") (pin "1") (pinfunction "1_1") (pintype "passive"))
    )
    (net (code "92") (name "Net-(Q1-NS1)") (class "Default")
      (node (ref "Q1") (pin "1") (pinfunction "NS1_1") (pintype "passive"))
      (node (ref "Q2") (pin "1") (pinfunction "NS1_1") (pintype "passive"))
      (node (ref "R21") (pin "2") (pinfunction "2_2") (pintype "passive"))
      (node (ref "R22") (pin "2") (pinfunction "2_2") (pintype "passive"))
      (node (ref "R27") (pin "2") (pinfunction "2_2") (pintype "passive"))
      (node (ref "R32") (pin "1") (pinfunction "1_1") (pintype "passive"))
    )
    (net (code "93") (name "Net-(Q1-PG2)") (class "Default")
      (node (ref "Q1") (pin "4") (pinfunction "PG2_4") (pintype "passive"))
      (node (ref "R18") (pin "2") (pinfunction "2_2") (pintype "passive"))
      (node (ref "R9") (pin "1") (pinfunction "1_1") (pintype "passive"))
    )
    (net (code "94") (name "Net-(Q2-NG1)") (class "Default")
      (node (ref "Q2") (pin "2") (pinfunction "NG1_2") (pintype "passive"))
      (node (ref "R21") (pin "1") (pinfunction "1_1") (pintype "passive"))
      (node (ref "R30") (pin "1") (pinfunction "1_1") (pintype "passive"))
    )
    (net (code "95") (name "Net-(Q2-PG2)") (class "Default")
      (node (ref "Q2") (pin "4") (pinfunction "PG2_4") (pintype "passive"))
      (node (ref "R10") (pin "1") (pinfunction "1_1") (pintype "passive"))
      (node (ref "R19") (pin "2") (pinfunction "2_2") (pintype "passive"))
    )
    (net (code "96") (name "Net-(Q3-B)") (class "Default")
      (node (ref "Q3") (pin "1") (pinfunction "B_1") (pintype "passive"))
      (node (ref "R26") (pin "1") (pinfunction "1_1") (pintype "passive"))
      (node (ref "R28") (pin "2") (pinfunction "2_2") (pintype "passive"))
    )
    (net (code "97") (name "Net-(Q3-C)") (class "Default")
      (node (ref "Q3") (pin "3") (pinfunction "C_3") (pintype "passive"))
      (node (ref "R18") (pin "1") (pinfunction "1_1") (pintype "passive"))
    )
    (net (code "98") (name "Net-(Q4-B)") (class "Default")
      (node (ref "Q4") (pin "1") (pinfunction "B_1") (pintype "passive"))
      (node (ref "R25") (pin "2") (pinfunction "2_2") (pintype "passive"))
      (node (ref "R31") (pin "1") (pinfunction "1_1") (pintype "passive"))
    )
    (net (code "99") (name "Net-(Q4-C)") (class "Default")
      (node (ref "Q4") (pin "3") (pinfunction "C_3") (pintype "passive"))
      (node (ref "R19") (pin "1") (pinfunction "1_1") (pintype "passive"))
    )
    (net (code "100") (name "Net-(Q5-NG1)") (class "Default")
      (node (ref "Q5") (pin "2") (pinfunction "NG1_2") (pintype "passive"))
      (node (ref "R49") (pin "2") (pinfunction "2_2") (pintype "passive"))
      (node (ref "R54") (pin "1") (pinfunction "1_1") (pintype "passive"))
    )
    (net (code "101") (name "Net-(Q5-PG2)") (class "Default")
      (node (ref "Q5") (pin "4") (pinfunction "PG2_4") (pintype "passive"))
      (node (ref "R45") (pin "1") (pinfunction "1_1") (pintype "passive"))
      (node (ref "R47") (pin "2") (pinfunction "2_2") (pintype "passive"))
    )
    (net (code "102") (name "Net-(Q6-NG1)") (class "Default")
      (node (ref "Q6") (pin "2") (pinfunction "NG1_2") (pintype "passive"))
      (node (ref "R50") (pin "2") (pinfunction "2_2") (pintype "passive"))
      (node (ref "R55") (pin "1") (pinfunction "1_1") (pintype "passive"))
    )
    (net (code "103") (name "Net-(Q6-PG2)") (class "Default")
      (node (ref "Q6") (pin "4") (pinfunction "PG2_4") (pintype "passive"))
      (node (ref "R46") (pin "1") (pinfunction "1_1") (pintype "passive"))
      (node (ref "R48") (pin "2") (pinfunction "2_2") (pintype "passive"))
    )
    (net (code "104") (name "Net-(Q7-B)") (class "Default")
      (node (ref "Q7") (pin "1") (pinfunction "B_1") (pintype "passive"))
      (node (ref "R52") (pin "1") (pinfunction "1_1") (pintype "passive"))
      (node (ref "R53") (pin "2") (pinfunction "2_2") (pintype "passive"))
    )
    (net (code "105") (name "Net-(Q7-C)") (class "Default")
      (node (ref "Q7") (pin "3") (pinfunction "C_3") (pintype "passive"))
      (node (ref "R47") (pin "1") (pinfunction "1_1") (pintype "passive"))
    )
    (net (code "106") (name "Net-(Q8-B)") (class "Default")
      (node (ref "Q8") (pin "1") (pinfunction "B_1") (pintype "passive"))
      (node (ref "R51") (pin "2") (pinfunction "2_2") (pintype "passive"))
      (node (ref "R56") (pin "2") (pinfunction "2_2") (pintype "passive"))
    )
    (net (code "107") (name "Net-(Q8-C)") (class "Default")
      (node (ref "Q8") (pin "3") (pinfunction "C_3") (pintype "passive"))
      (node (ref "R48") (pin "1") (pinfunction "1_1") (pintype "passive"))
    )
    (net (code "108") (name "Net-(Q9-NG1)") (class "Default")
      (node (ref "Q9") (pin "2") (pinfunction "NG1_2") (pintype "passive"))
      (node (ref "R68") (pin "2") (pinfunction "2_2") (pintype "passive"))
      (node (ref "R72") (pin "1") (pinfunction "1_1") (pintype "passive"))
    )
    (net (code "109") (name "Net-(Q9-PG2)") (class "Default")
      (node (ref "Q9") (pin "4") (pinfunction "PG2_4") (pintype "passive"))
      (node (ref "R60") (pin "1") (pinfunction "1_1") (pintype "passive"))
      (node (ref "R63") (pin "2") (pinfunction "2_2") (pintype "passive"))
    )
    (net (code "110") (name "Net-(Q10-NG1)") (class "Default")
      (node (ref "Q10") (pin "2") (pinfunction "NG1_2") (pintype "passive"))
      (node (ref "R67") (pin "2") (pinfunction "2_2") (pintype "passive"))
      (node (ref "R73") (pin "1") (pinfunction "1_1") (pintype "passive"))
    )
    (net (code "111") (name "Net-(Q10-NS1)") (class "Default")
      (node (ref "Q10") (pin "1") (pinfunction "NS1_1") (pintype "passive"))
      (node (ref "Q5") (pin "1") (pinfunction "NS1_1") (pintype "passive"))
      (node (ref "Q6") (pin "1") (pinfunction "NS1_1") (pintype "passive"))
      (node (ref "Q9") (pin "1") (pinfunction "NS1_1") (pintype "passive"))
      (node (ref "R49") (pin "1") (pinfunction "1_1") (pintype "passive"))
      (node (ref "R50") (pin "1") (pinfunction "1_1") (pintype "passive"))
      (node (ref "R67") (pin "1") (pinfunction "1_1") (pintype "passive"))
      (node (ref "R68") (pin "1") (pinfunction "1_1") (pintype "passive"))
      (node (ref "R76") (pin "2") (pinfunction "2_2") (pintype "passive"))
      (node (ref "R77") (pin "1") (pinfunction "1_1") (pintype "passive"))
    )
    (net (code "112") (name "Net-(Q10-PG2)") (class "Default")
      (node (ref "Q10") (pin "4") (pinfunction "PG2_4") (pintype "passive"))
      (node (ref "R61") (pin "1") (pinfunction "1_1") (pintype "passive"))
      (node (ref "R66") (pin "2") (pinfunction "2_2") (pintype "passive"))
    )
    (net (code "113") (name "Net-(Q11-B)") (class "Default")
      (node (ref "Q11") (pin "1") (pinfunction "B_1") (pintype "passive"))
      (node (ref "R70") (pin "1") (pinfunction "1_1") (pintype "passive"))
      (node (ref "R71") (pin "2") (pinfunction "2_2") (pintype "passive"))
    )
    (net (code "114") (name "Net-(Q11-C)") (class "Default")
      (node (ref "Q11") (pin "3") (pinfunction "C_3") (pintype "passive"))
      (node (ref "R63") (pin "1") (pinfunction "1_1") (pintype "passive"))
    )
    (net (code "115") (name "Net-(Q12-B)") (class "Default")
      (node (ref "Q12") (pin "1") (pinfunction "B_1") (pintype "passive"))
      (node (ref "R69") (pin "2") (pinfunction "2_2") (pintype "passive"))
      (node (ref "R74") (pin "2") (pinfunction "2_2") (pintype "passive"))
    )
    (net (code "116") (name "Net-(Q12-C)") (class "Default")
      (node (ref "Q12") (pin "3") (pinfunction "C_3") (pintype "passive"))
      (node (ref "R66") (pin "1") (pinfunction "1_1") (pintype "passive"))
    )
    (net (code "117") (name "Net-(Q13-G)") (class "Default")
      (node (ref "Q13") (pin "1") (pinfunction "G_1") (pintype "passive"))
      (node (ref "R88") (pin "1") (pinfunction "1_1") (pintype "passive"))
      (node (ref "R94") (pin "2") (pinfunction "2_2") (pintype "passive"))
    )
    (net (code "118") (name "Net-(Q14-G)") (class "Default")
      (node (ref "Q14") (pin "1") (pinfunction "G_1") (pintype "passive"))
      (node (ref "R89") (pin "1") (pinfunction "1_1") (pintype "passive"))
      (node (ref "R95") (pin "2") (pinfunction "2_2") (pintype "passive"))
    )
    (net (code "119") (name "Net-(Q15-G)") (class "Default")
      (node (ref "Q15") (pin "1") (pinfunction "G_1") (pintype "passive"))
      (node (ref "R91") (pin "1") (pinfunction "1_1") (pintype "passive"))
      (node (ref "R97") (pin "2") (pinfunction "2_2") (pintype "passive"))
    )
    (net (code "120") (name "Net-(Q16-G)") (class "Default")
      (node (ref "Q16") (pin "1") (pinfunction "G_1") (pintype "passive"))
      (node (ref "R90") (pin "1") (pinfunction "1_1") (pintype "passive"))
      (node (ref "R96") (pin "2") (pinfunction "2_2") (pintype "passive"))
    )
    (net (code "121") (name "Net-(Q17-B)") (class "Default")
      (node (ref "Q17") (pin "1") (pinfunction "B_1") (pintype "passive"))
      (node (ref "R106") (pin "2") (pinfunction "2_2") (pintype "passive"))
      (node (ref "R99") (pin "1") (pinfunction "1_1") (pintype "passive"))
    )
    (net (code "122") (name "Net-(Q17-C)") (class "Default")
      (node (ref "Q17") (pin "3") (pinfunction "C_3") (pintype "passive"))
      (node (ref "R96") (pin "1") (pinfunction "1_1") (pintype "passive"))
    )
    (net (code "123") (name "Net-(Q18-G)") (class "Default")
      (node (ref "Q18") (pin "1") (pinfunction "G_1") (pintype "passive"))
      (node (ref "R104") (pin "1") (pinfunction "1_1") (pintype "passive"))
      (node (ref "R112") (pin "2") (pinfunction "2_2") (pintype "passive"))
    )
    (net (code "124") (name "Net-(Q18-S)") (class "Default")
      (node (ref "Q18") (pin "2") (pinfunction "S_2") (pintype "passive"))
      (node (ref "Q19") (pin "2") (pinfunction "S_2") (pintype "passive"))
      (node (ref "R104") (pin "2") (pinfunction "2_2") (pintype "passive"))
      (node (ref "R105") (pin "2") (pinfunction "2_2") (pintype "passive"))
      (node (ref "R116") (pin "1") (pinfunction "1_1") (pintype "passive"))
      (node (ref "R120") (pin "1") (pinfunction "1_1") (pintype "passive"))
    )
    (net (code "125") (name "Net-(Q19-G)") (class "Default")
      (node (ref "Q19") (pin "1") (pinfunction "G_1") (pintype "passive"))
      (node (ref "R105") (pin "1") (pinfunction "1_1") (pintype "passive"))
      (node (ref "R113") (pin "2") (pinfunction "2_2") (pintype "passive"))
    )
    (net (code "126") (name "Net-(Q20-G)") (class "Default")
      (node (ref "Q20") (pin "1") (pinfunction "G_1") (pintype "passive"))
      (node (ref "R107") (pin "1") (pinfunction "1_1") (pintype "passive"))
      (node (ref "R114") (pin "2") (pinfunction "2_2") (pintype "passive"))
    )
    (net (code "127") (name "Net-(Q20-S)") (class "Default")
      (node (ref "Q20") (pin "2") (pinfunction "S_2") (pintype "passive"))
      (node (ref "Q21") (pin "2") (pinfunction "S_2") (pintype "passive"))
      (node (ref "R107") (pin "2") (pinfunction "2_2") (pintype "passive"))
      (node (ref "R108") (pin "2") (pinfunction "2_2") (pintype "passive"))
      (node (ref "R117") (pin "1") (pinfunction "1_1") (pintype "passive"))
      (node (ref "R121") (pin "1") (pinfunction "1_1") (pintype "passive"))
    )
    (net (code "128") (name "Net-(Q21-G)") (class "Default")
      (node (ref "Q21") (pin "1") (pinfunction "G_1") (pintype "passive"))
      (node (ref "R108") (pin "1") (pinfunction "1_1") (pintype "passive"))
      (node (ref "R115") (pin "2") (pinfunction "2_2") (pintype "passive"))
    )
    (net (code "129") (name "Net-(Q22-B)") (class "Default")
      (node (ref "Q22") (pin "1") (pinfunction "B_1") (pintype "passive"))
      (node (ref "R102") (pin "1") (pinfunction "1_1") (pintype "passive"))
      (node (ref "R103") (pin "2") (pinfunction "2_2") (pintype "passive"))
    )
    (net (code "130") (name "Net-(Q22-C)") (class "Default")
      (node (ref "Q22") (pin "3") (pinfunction "C_3") (pintype "passive"))
      (node (ref "R94") (pin "1") (pinfunction "1_1") (pintype "passive"))
    )
    (net (code "131") (name "Net-(Q23-B)") (class "Default")
      (node (ref "Q23") (pin "1") (pinfunction "B_1") (pintype "passive"))
      (node (ref "R110") (pin "2") (pinfunction "2_2") (pintype "passive"))
      (node (ref "R98") (pin "2") (pinfunction "2_2") (pintype "passive"))
    )
    (net (code "132") (name "Net-(Q23-C)") (class "Default")
      (node (ref "Q23") (pin "3") (pinfunction "C_3") (pintype "passive"))
      (node (ref "R95") (pin "1") (pinfunction "1_1") (pintype "passive"))
    )
    (net (code "133") (name "Net-(Q24-B)") (class "Default")
      (node (ref "Q24") (pin "1") (pinfunction "B_1") (pintype "passive"))
      (node (ref "R100") (pin "2") (pinfunction "2_2") (pintype "passive"))
      (node (ref "R109") (pin "2") (pinfunction "2_2") (pintype "passive"))
    )
    (net (code "134") (name "Net-(Q24-C)") (class "Default")
      (node (ref "Q24") (pin "3") (pinfunction "C_3") (pintype "passive"))
      (node (ref "R97") (pin "1") (pinfunction "1_1") (pintype "passive"))
    )
    (net (code "135") (name "Net-(Q25-B)") (class "Default")
      (node (ref "Q25") (pin "1") (pinfunction "B_1") (pintype "passive"))
      (node (ref "R130") (pin "1") (pinfunction "1_1") (pintype "passive"))
    )
    (net (code "136") (name "Net-(R78-Pad2)") (class "Default")
      (node (ref "R78") (pin "2") (pinfunction "2_2") (pintype "passive"))
      (node (ref "R79") (pin "1") (pinfunction "1_1") (pintype "passive"))
      (node (ref "R82") (pin "1") (pinfunction "1_1") (pintype "passive"))
      (node (ref "U9") (pin "1") (pinfunction "1_1") (pintype "passive"))
    )
    (net (code "137") (name "Net-(R80-Pad2)") (class "Default")
      (node (ref "R80") (pin "2") (pinfunction "2_2") (pintype "passive"))
      (node (ref "R81") (pin "2") (pinfunction "2_2") (pintype "passive"))
      (node (ref "R83") (pin "1") (pinfunction "1_1") (pintype "passive"))
      (node (ref "U9") (pin "7") (pinfunction "7_7") (pintype "passive"))
    )
    (net (code "138") (name "Net-(R82-Pad2)") (class "Default")
      (node (ref "R82") (pin "2") (pinfunction "2_2") (pintype "passive"))
      (node (ref "R84") (pin "1") (pinfunction "1_1") (pintype "passive"))
      (node (ref "U9") (pin "2") (pinfunction "2_2") (pintype "passive"))
    )
    (net (code "139") (name "Net-(R83-Pad2)") (class "Default")
      (node (ref "R83") (pin "2") (pinfunction "2_2") (pintype "passive"))
      (node (ref "R85") (pin "1") (pinfunction "1_1") (pintype "passive"))
      (node (ref "U9") (pin "6") (pinfunction "6_6") (pintype "passive"))
    )
    (net (code "140") (name "Net-(R111-Pad1)") (class "Default")
      (node (ref "R111") (pin "1") (pinfunction "1_1") (pintype "passive"))
      (node (ref "R118") (pin "1") (pinfunction "1_1") (pintype "passive"))
      (node (ref "R123") (pin "2") (pinfunction "2_2") (pintype "passive"))
      (node (ref "U10") (pin "1") (pinfunction "1_1") (pintype "passive"))
    )
    (net (code "141") (name "Net-(R119-Pad1)") (class "Default")
      (node (ref "R119") (pin "1") (pinfunction "1_1") (pintype "passive"))
      (node (ref "R122") (pin "2") (pinfunction "2_2") (pintype "passive"))
      (node (ref "R124") (pin "2") (pinfunction "2_2") (pintype "passive"))
      (node (ref "U10") (pin "7") (pinfunction "7_7") (pintype "passive"))
    )
    (net (code "142") (name "Net-(R123-Pad1)") (class "Default")
      (node (ref "R123") (pin "1") (pinfunction "1_1") (pintype "passive"))
      (node (ref "R127") (pin "2") (pinfunction "2_2") (pintype "passive"))
      (node (ref "U10") (pin "2") (pinfunction "2_2") (pintype "passive"))
    )
    (net (code "143") (name "Net-(R124-Pad1)") (class "Default")
      (node (ref "R124") (pin "1") (pinfunction "1_1") (pintype "passive"))
      (node (ref "R128") (pin "2") (pinfunction "2_2") (pintype "passive"))
      (node (ref "U10") (pin "6") (pinfunction "6_6") (pintype "passive"))
    )
    (net (code "144") (name "Net-(U6-BOOT0)") (class "Default")
      (node (ref "R34") (pin "2") (pinfunction "2_2") (pintype "passive"))
      (node (ref "U6") (pin "44") (pinfunction "BOOT0_44") (pintype "input"))
    )
    (net (code "145") (name "Net-(U6-NRST)") (class "Default")
      (node (ref "C29") (pin "2") (pinfunction "2_2") (pintype "passive"))
      (node (ref "R35") (pin "1") (pinfunction "1_1") (pintype "passive"))
      (node (ref "U6") (pin "7") (pinfunction "NRST_7") (pintype "bidirectional"))
    )
    (net (code "146") (name "Net-(U6-OSC-IN{slash}PD0)") (class "Default")
      (node (ref "C26") (pin "2") (pinfunction "2_2") (pintype "passive"))
      (node (ref "U6") (pin "5") (pinfunction "OSC-IN/PD0_5") (pintype "input"))
      (node (ref "X1") (pin "2") (pinfunction "2_2") (pintype "passive"))
    )
    (net (code "147") (name "Net-(U6-OSC-OUT{slash}PD1)") (class "Default")
      (node (ref "C27") (pin "2") (pinfunction "2_2") (pintype "passive"))
      (node (ref "U6") (pin "6") (pinfunction "OSC-OUT/PD1_6") (pintype "output"))
      (node (ref "X1") (pin "1") (pinfunction "1_1") (pintype "passive"))
    )
    (net (code "148") (name "Net-(U8-A6)") (class "Default")
      (node (ref "R130") (pin "2") (pinfunction "2_2") (pintype "passive"))
      (node (ref "U8") (pin "8") (pinfunction "A6_8") (pintype "passive"))
    )
    (net (code "149") (name "VCC-5V") (class "Default")
      (node (ref "C10") (pin "1") (pinfunction "1_1") (pintype "passive"))
      (node (ref "C11") (pin "2") (pinfunction "2_2") (pintype "passive"))
      (node (ref "C12") (pin "2") (pinfunction "2_2") (pintype "passive"))
      (node (ref "C13") (pin "2") (pinfunction "2_2") (pintype "passive"))
      (node (ref "C14") (pin "2") (pinfunction "2_2") (pintype "passive"))
      (node (ref "C20") (pin "2") (pinfunction "2_2") (pintype "passive"))
      (node (ref "C40") (pin "1") (pinfunction "1_1") (pintype "passive"))
      (node (ref "C5") (pin "1") (pinfunction "1_1") (pintype "passive"))
      (node (ref "C57") (pin "1") (pinfunction "1_1") (pintype "passive"))
      (node (ref "C58") (pin "1") (pinfunction "1_1") (pintype "passive"))
      (node (ref "C60") (pin "1") (pinfunction "1_1") (pintype "passive"))
      (node (ref "C63") (pin "2") (pinfunction "2_2") (pintype "passive"))
      (node (ref "C69") (pin "2") (pinfunction "2_2") (pintype "passive"))
      (node (ref "C72") (pin "2") (pinfunction "2_2") (pintype "passive"))
      (node (ref "J1") (pin "8") (pinfunction "8_8") (pintype "passive"))
      (node (ref "J2") (pin "6") (pinfunction "6_6") (pintype "passive"))
      (node (ref "J3") (pin "1") (pinfunction "1_1") (pintype "passive"))
      (node (ref "J4") (pin "1") (pinfunction "1_1") (pintype "passive"))
      (node (ref "R1") (pin "2") (pinfunction "2_2") (pintype "passive"))
      (node (ref "R14") (pin "2") (pinfunction "2_2") (pintype "passive"))
      (node (ref "R15") (pin "2") (pinfunction "2_2") (pintype "passive"))
      (node (ref "R16") (pin "2") (pinfunction "2_2") (pintype "passive"))
      (node (ref "R17") (pin "2") (pinfunction "2_2") (pintype "passive"))
      (node (ref "R2") (pin "2") (pinfunction "2_2") (pintype "passive"))
      (node (ref "R3") (pin "2") (pinfunction "2_2") (pintype "passive"))
      (node (ref "R4") (pin "2") (pinfunction "2_2") (pintype "passive"))
      (node (ref "R65") (pin "2") (pinfunction "2_2") (pintype "passive"))
      (node (ref "U1") (pin "14") (pinfunction "VCC_14") (pintype "power_in"))
      (node (ref "U11") (pin "8") (pinfunction "VCC_8") (pintype "passive"))
      (node (ref "U12") (pin "8") (pinfunction "VCC_8") (pintype "passive"))
      (node (ref "U13") (pin "8") (pinfunction "VCC_8") (pintype "passive"))
      (node (ref "U2") (pin "13") (pinfunction "A_13") (pintype "input"))
      (node (ref "U2") (pin "14") (pinfunction "VCC_14") (pintype "power_in"))
      (node (ref "U3") (pin "8") (pinfunction "VCC_8") (pintype "passive"))
      (node (ref "U4") (pin "1") (pinfunction "VIN_1") (pintype "passive"))
      (node (ref "U4") (pin "3") (pinfunction "CE_3") (pintype "passive"))
      (node (ref "U5") (pin "14") (pinfunction "VCC_14") (pintype "power_in"))
      (node (ref "U7") (pin "10") (pinfunction "B_10") (pintype "input"))
      (node (ref "U7") (pin "12") (pinfunction "A_12") (pintype "input"))
      (node (ref "U7") (pin "13") (pinfunction "B_13") (pintype "input"))
      (node (ref "U7") (pin "14") (pinfunction "VCC_14") (pintype "power_in"))
      (node (ref "U7") (pin "9") (pinfunction "A_9") (pintype "input"))
    )
    (net (code "150") (name "VCC-22V") (class "Default")
      (node (ref "F2") (pin "2") (pinfunction "2_2") (pintype "passive"))
      (node (ref "J1") (pin "2") (pinfunction "2_2") (pintype "passive"))
    )
    (net (code "151") (name "VCC-22V-O") (class "Default")
      (node (ref "C18") (pin "1") (pinfunction "1_1") (pintype "passive"))
      (node (ref "C2") (pin "1") (pinfunction "1_1") (pintype "passive"))
      (node (ref "C39") (pin "1") (pinfunction "1_1") (pintype "passive"))
      (node (ref "C4") (pin "1") (pinfunction "1_1") (pintype "passive"))
      (node (ref "D7") (pin "2") (pinfunction "K_2") (pintype "passive"))
      (node (ref "D8") (pin "2") (pinfunction "K_2") (pintype "passive"))
      (node (ref "Q1") (pin "3") (pinfunction "PS2_3") (pintype "passive"))
      (node (ref "Q10") (pin "3") (pinfunction "PS2_3") (pintype "passive"))
      (node (ref "Q2") (pin "3") (pinfunction "PS2_3") (pintype "passive"))
      (node (ref "Q5") (pin "3") (pinfunction "PS2_3") (pintype "passive"))
      (node (ref "Q6") (pin "3") (pinfunction "PS2_3") (pintype "passive"))
      (node (ref "Q9") (pin "3") (pinfunction "PS2_3") (pintype "passive"))
      (node (ref "R10") (pin "2") (pinfunction "2_2") (pintype "passive"))
      (node (ref "R45") (pin "2") (pinfunction "2_2") (pintype "passive"))
      (node (ref "R46") (pin "2") (pinfunction "2_2") (pintype "passive"))
      (node (ref "R58") (pin "2") (pinfunction "2_2") (pintype "passive"))
      (node (ref "R6") (pin "2") (pinfunction "2_2") (pintype "passive"))
      (node (ref "R60") (pin "2") (pinfunction "2_2") (pintype "passive"))
      (node (ref "R61") (pin "2") (pinfunction "2_2") (pintype "passive"))
      (node (ref "R7") (pin "2") (pinfunction "2_2") (pintype "passive"))
      (node (ref "R9") (pin "2") (pinfunction "2_2") (pintype "passive"))
    )
    (net (code "152") (name "VCC-24V") (class "Default")
      (node (ref "D6") (pin "2") (pinfunction "K_2") (pintype "passive"))
      (node (ref "F1") (pin "2") (pinfunction "2_2") (pintype "passive"))
      (node (ref "J1") (pin "1") (pinfunction "1_1") (pintype "passive"))
    )
    (net (code "153") (name "unconnected-(J4-Pad5)") (class "Default")
      (node (ref "J4") (pin "5") (pinfunction "5_5") (pintype "passive"))
    )
    (net (code "154") (name "unconnected-(J9-Pad1)") (class "Default")
      (node (ref "J9") (pin "1") (pinfunction "1_1") (pintype "passive"))
    )
    (net (code "155") (name "unconnected-(J9-Pad2)") (class "Default")
      (node (ref "J9") (pin "2") (pinfunction "2_2") (pintype "passive"))
    )
    (net (code "156") (name "unconnected-(J9-Pad3)") (class "Default")
      (node (ref "J9") (pin "3") (pinfunction "3_3") (pintype "passive"))
    )
    (net (code "157") (name "unconnected-(U2F-Y-Pad12)") (class "Default")
      (node (ref "U2") (pin "12") (pinfunction "Y_12") (pintype "output"))
    )
    (net (code "158") (name "unconnected-(U4-NC-Pad4)") (class "Default")
      (node (ref "U4") (pin "4") (pinfunction "NC_4") (pintype "passive"))
    )
    (net (code "159") (name "unconnected-(U6-PA5-Pad15)") (class "Default")
      (node (ref "U6") (pin "15") (pinfunction "PA5_15") (pintype "bidirectional"))
    )
    (net (code "160") (name "unconnected-(U6-PB12-Pad25)") (class "Default")
      (node (ref "U6") (pin "25") (pinfunction "PB12_25") (pintype "bidirectional"))
    )
    (net (code "161") (name "unconnected-(U7C-Y-Pad8)") (class "Default")
      (node (ref "U7") (pin "8") (pinfunction "Y_8") (pintype "output"))
    )
    (net (code "162") (name "unconnected-(U7D-Y-Pad11)") (class "Default")
      (node (ref "U7") (pin "11") (pinfunction "Y_11") (pintype "output"))
    )
    (net (code "163") (name "unconnected-(U8-A7-Pad9)") (class "Default")
      (node (ref "U8") (pin "9") (pinfunction "A7_9") (pintype "passive"))
    )
  )
)
